# io-board-d-4.net
KiCad netlist of a schematic drawn in EAGLE
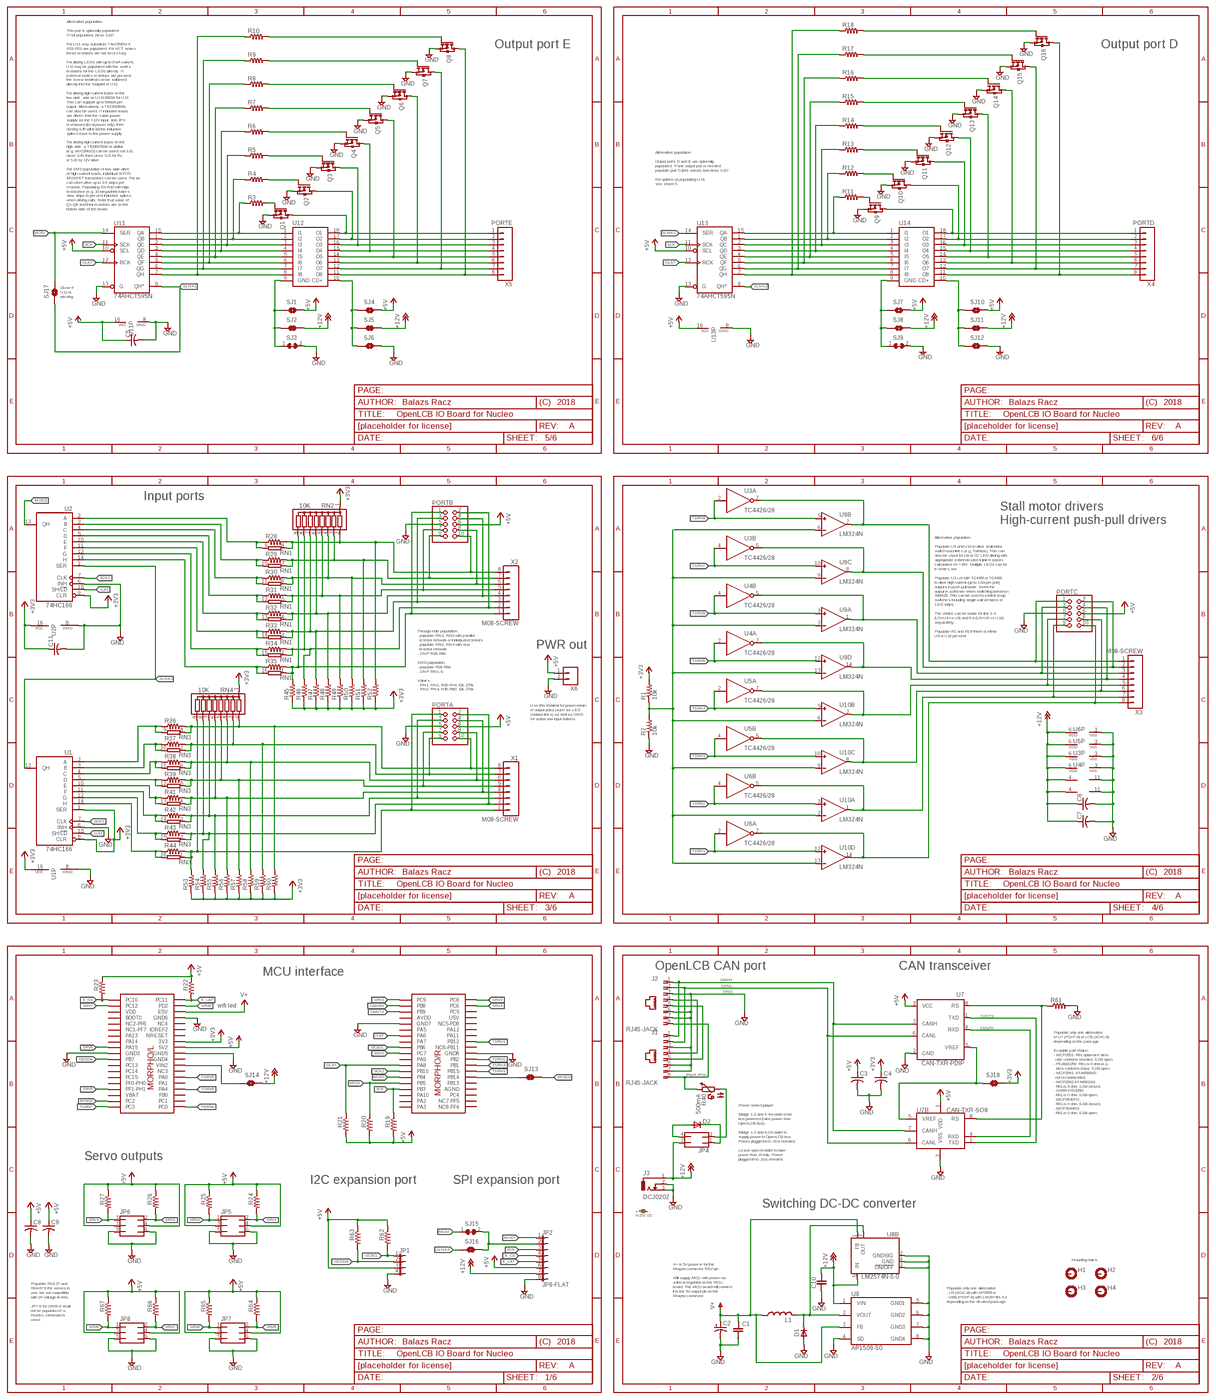
[diagram p0: schematic, sheet 1, overview]
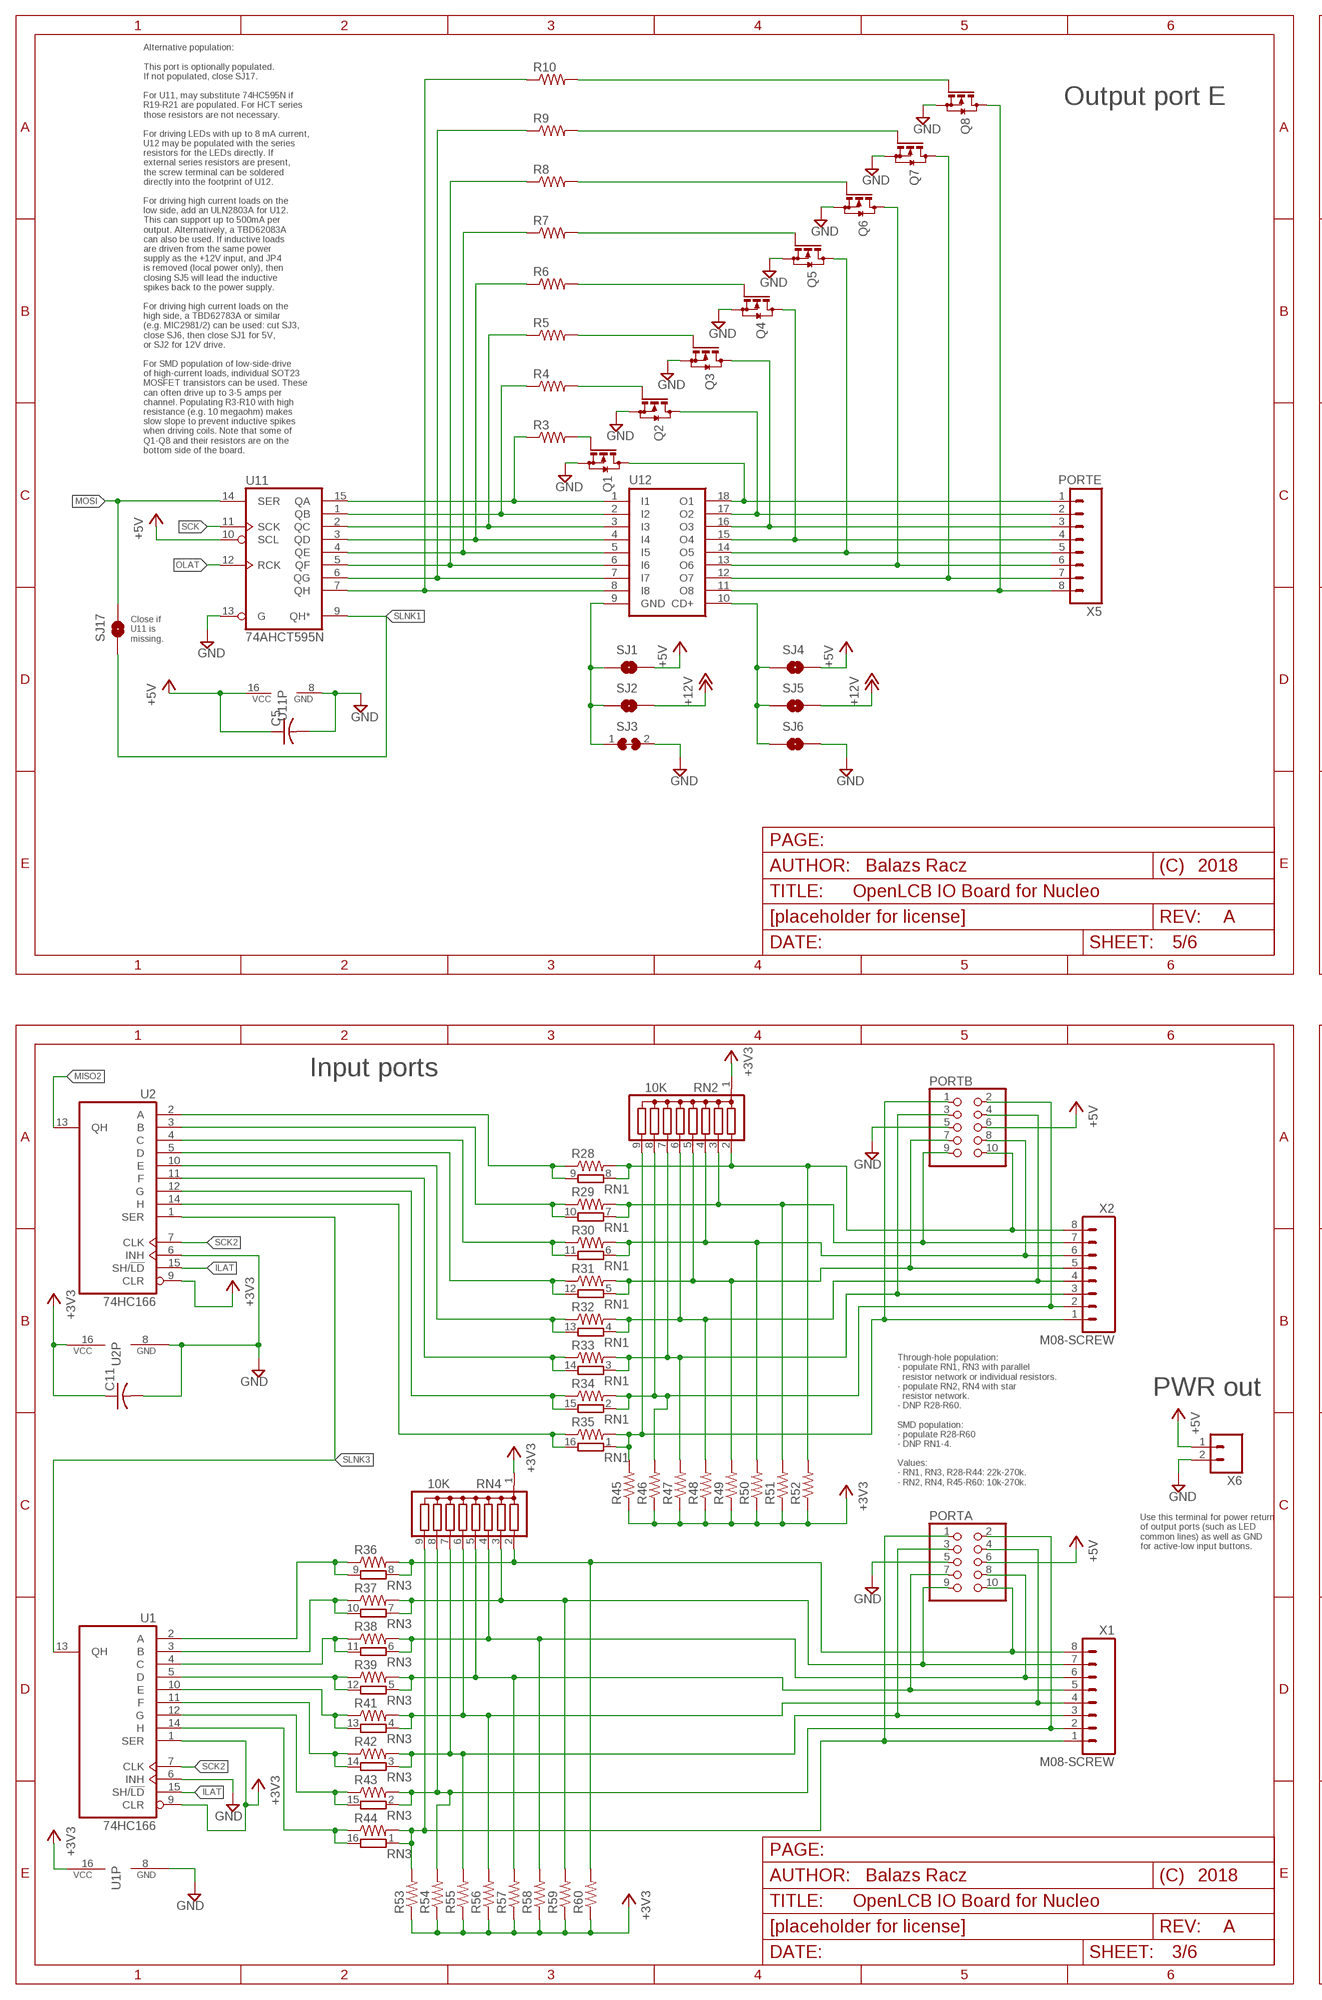
[diagram p1: schematic, sheet 1, part 1 of 4]
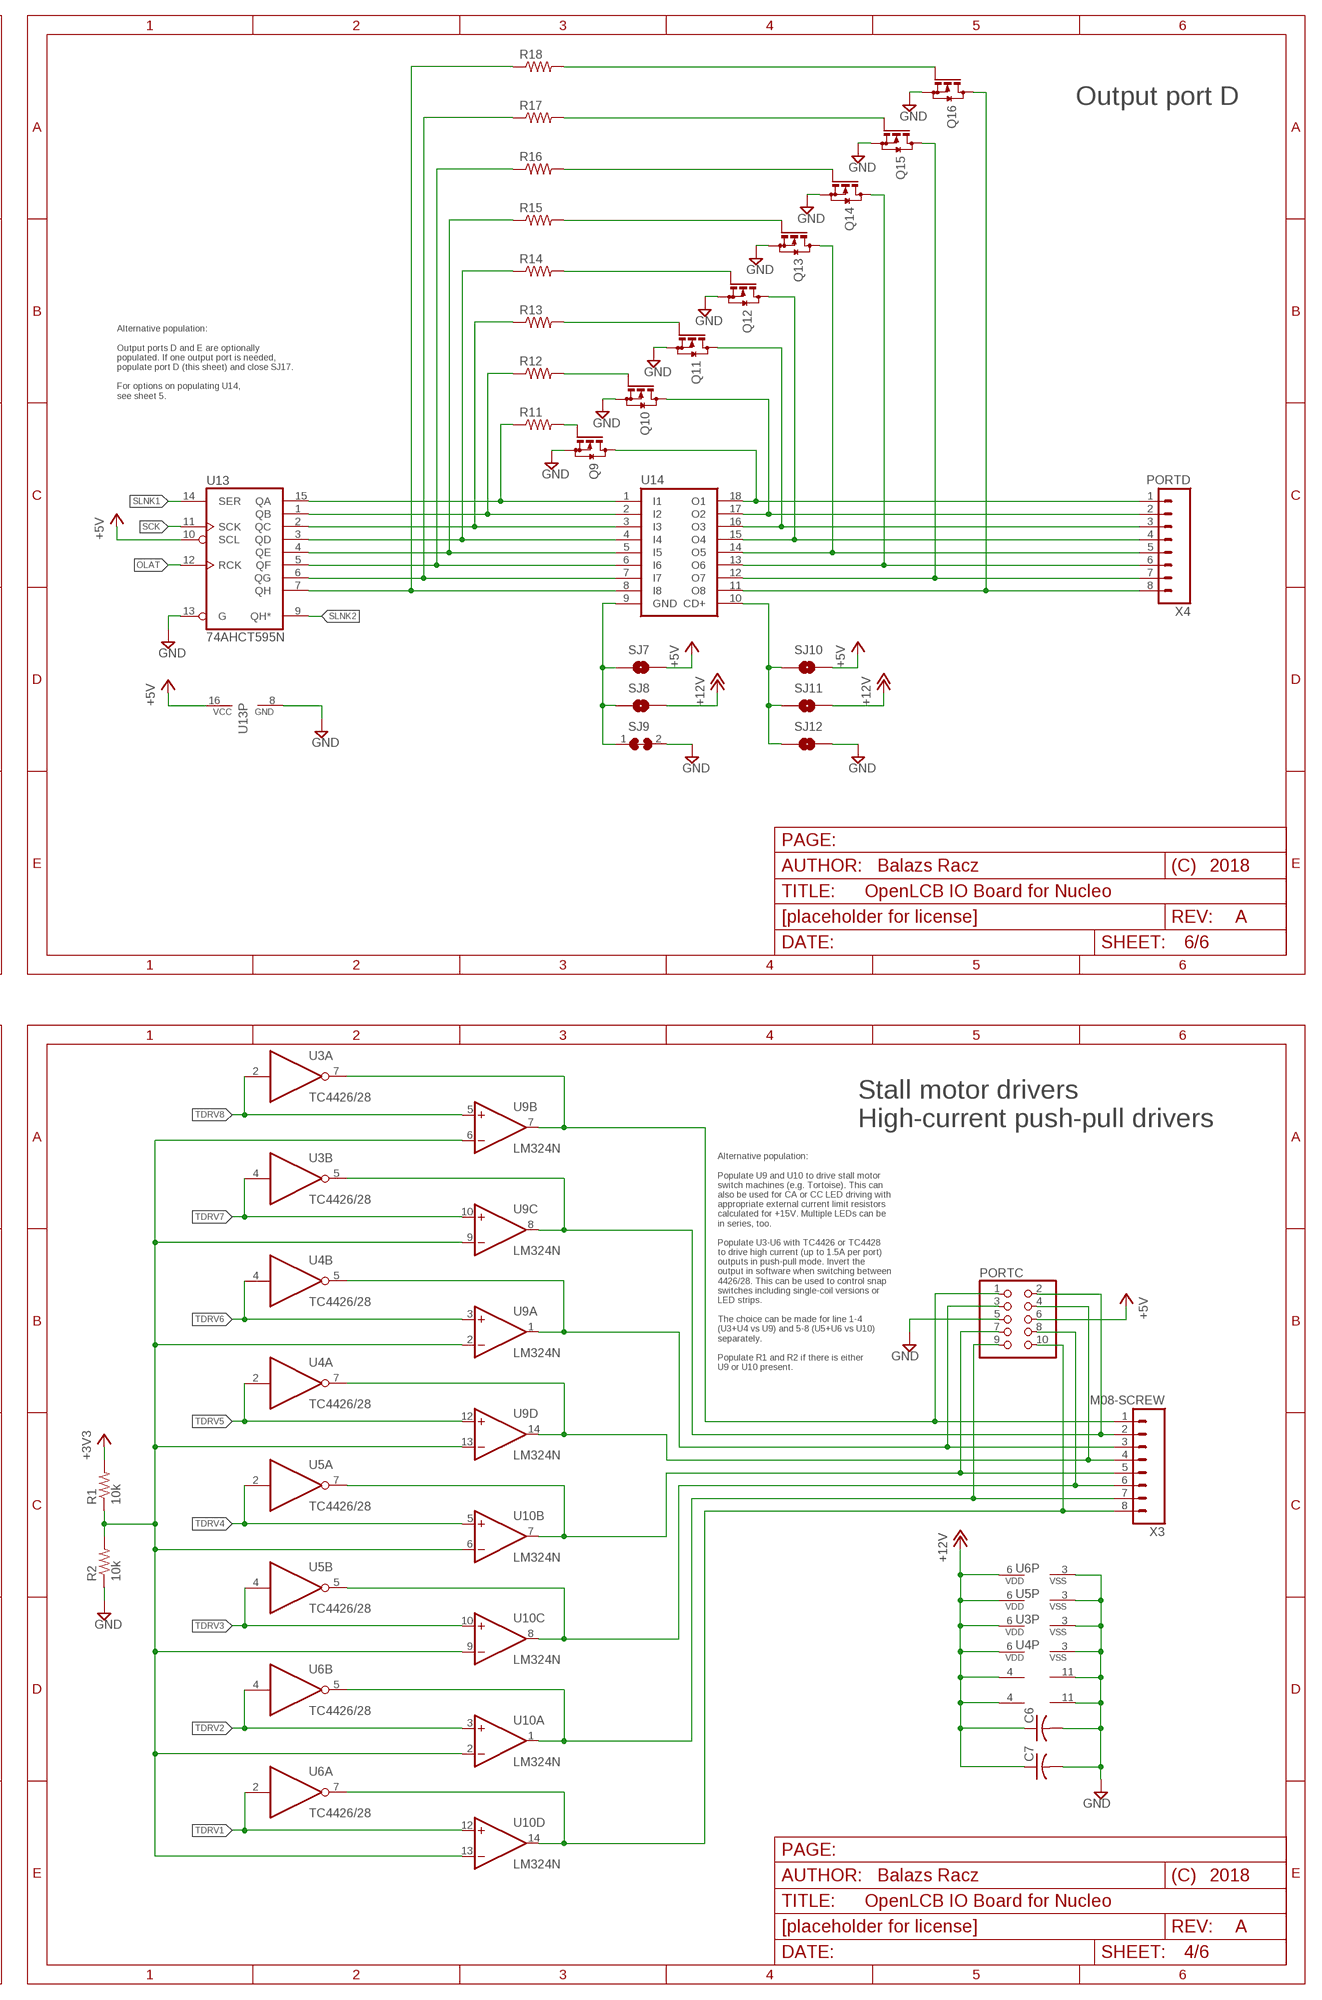
[diagram p2: schematic, sheet 1, part 2 of 4]
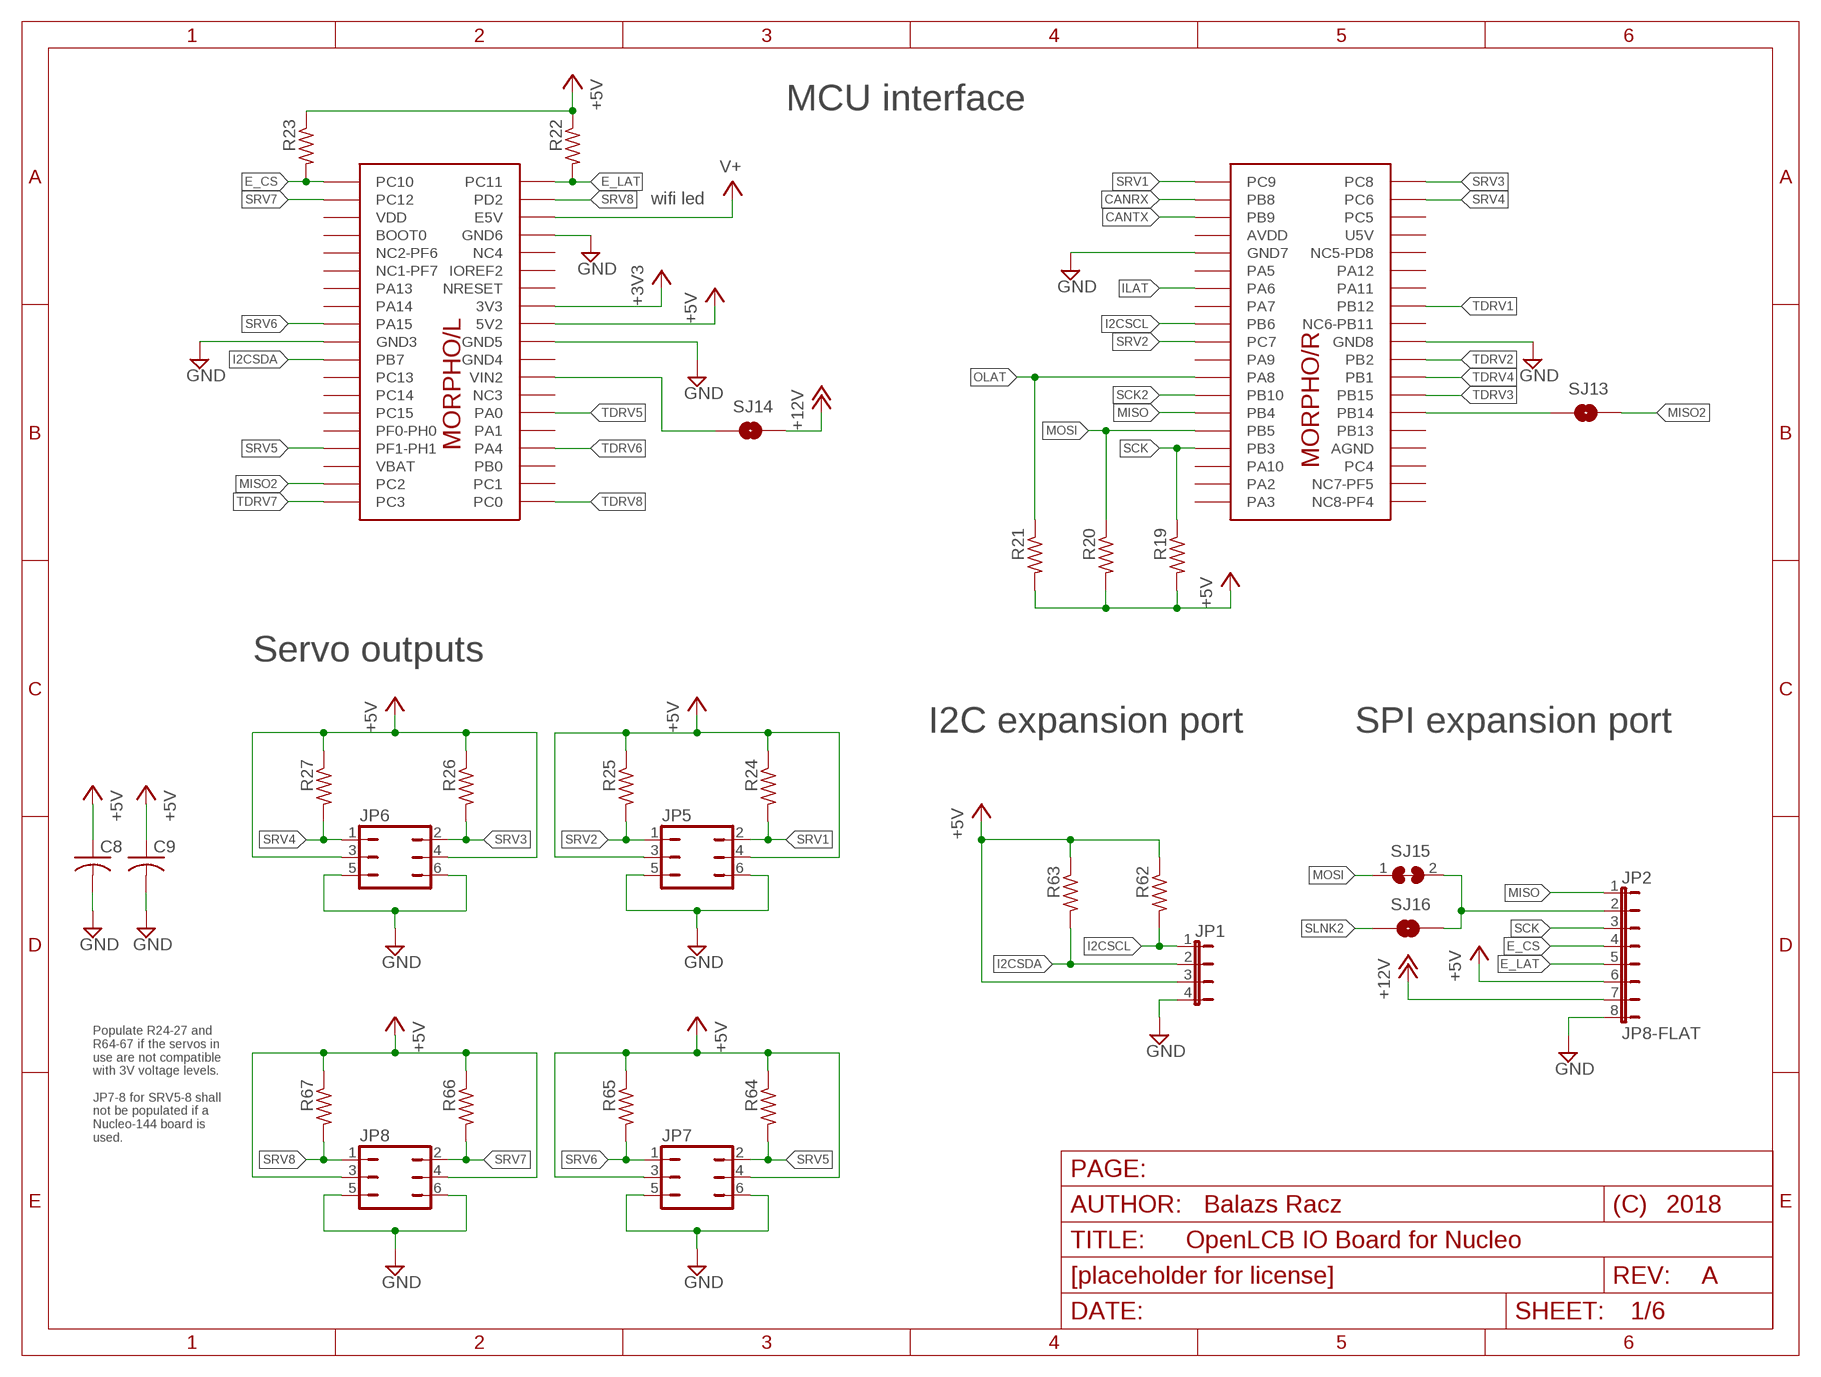
[diagram p3: schematic, sheet 1, part 3 of 4]
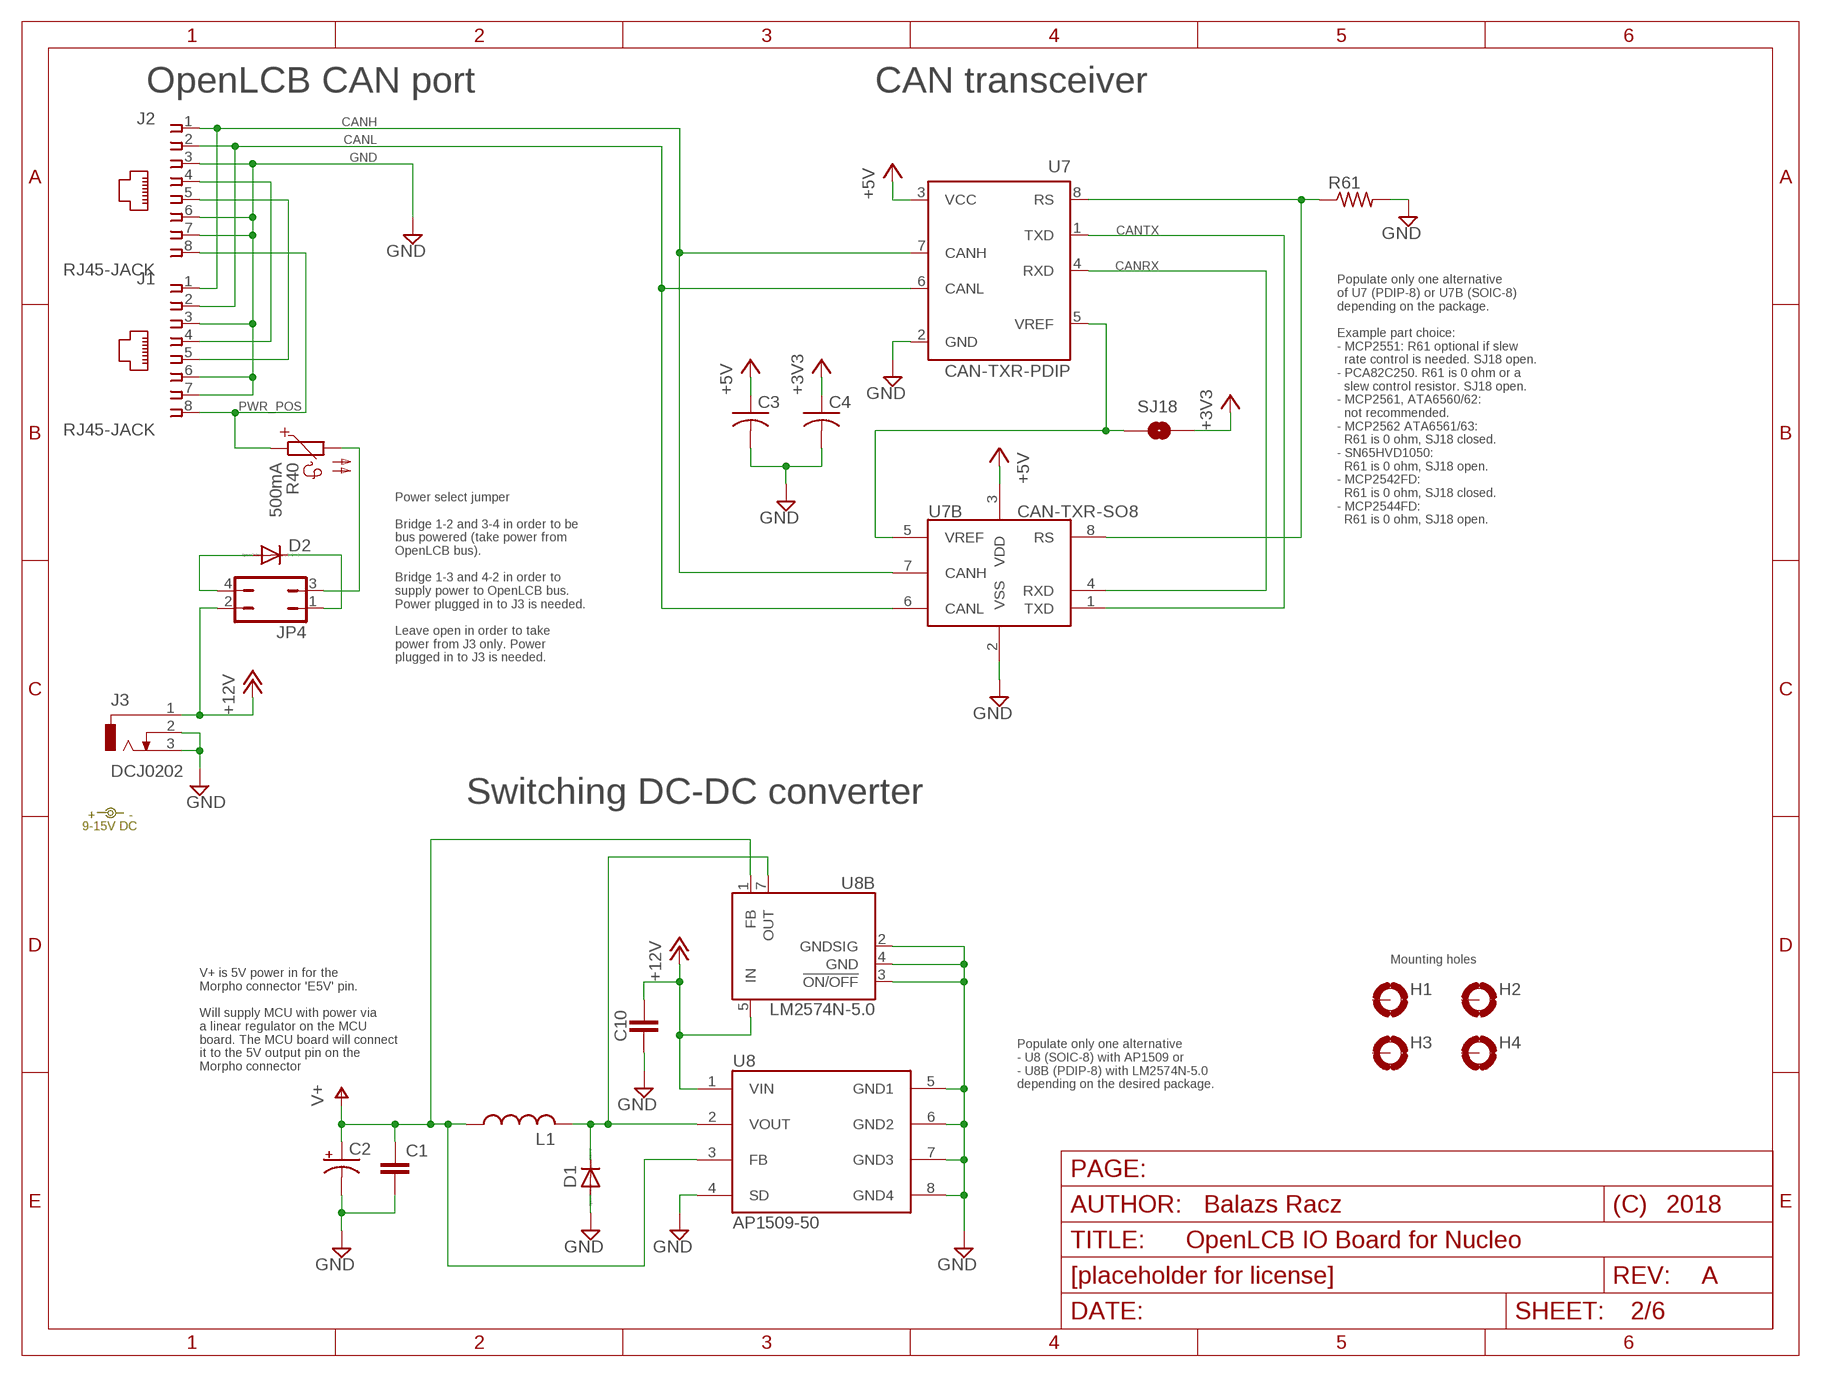
[diagram p4: schematic, sheet 1, part 4 of 4]

(export (version "E")
  (design (tool "Eeschema 10.0.6"))
  (components
    (comp (ref "+12V")
      (value "9-15V DC")
      (footprint "eagle-import:POWER_USAGE")
      (libsource (lib "eagle-import") (part "DOC-POWER_LABEL"))
    )
    (comp (ref "C1")
      (value "C-EUC1206")
      (footprint "eagle-import:C1206")
      (libsource (lib "eagle-import") (part "C-EUC1206"))
    )
    (comp (ref "C2")
      (value "CPOL-USE2.5-5")
      (footprint "eagle-import:E2,5-5")
      (libsource (lib "eagle-import") (part "CPOL-USE2.5-5"))
    )
    (comp (ref "C3")
      (value "C-USC0805")
      (footprint "eagle-import:C0805")
      (libsource (lib "eagle-import") (part "C-USC0805"))
    )
    (comp (ref "C4")
      (value "C-USC0805")
      (footprint "eagle-import:C0805")
      (libsource (lib "eagle-import") (part "C-USC0805"))
    )
    (comp (ref "C5")
      (value "C-USC0805")
      (footprint "eagle-import:C0805")
      (libsource (lib "eagle-import") (part "C-USC0805"))
    )
    (comp (ref "C6")
      (value "C-USC1206")
      (footprint "eagle-import:C1206")
      (libsource (lib "eagle-import") (part "C-USC1206"))
    )
    (comp (ref "C7")
      (value "C-USC1206")
      (footprint "eagle-import:C1206")
      (libsource (lib "eagle-import") (part "C-USC1206"))
    )
    (comp (ref "C8")
      (value "C-USC1206")
      (footprint "eagle-import:C1206")
      (libsource (lib "eagle-import") (part "C-USC1206"))
    )
    (comp (ref "C9")
      (value "C-USC1206")
      (footprint "eagle-import:C1206")
      (libsource (lib "eagle-import") (part "C-USC1206"))
    )
    (comp (ref "C10")
      (value "C-EUC1206")
      (footprint "eagle-import:C1206")
      (libsource (lib "eagle-import") (part "C-EUC1206"))
    )
    (comp (ref "C11")
      (value "C-USC0805")
      (footprint "eagle-import:C0805")
      (libsource (lib "eagle-import") (part "C-USC0805"))
    )
    (comp (ref "D1")
      (value "DIODE-DO41-7.6")
      (footprint "eagle-import:DO41-7.6")
      (libsource (lib "eagle-import") (part "DIODE-DO41-7.6"))
    )
    (comp (ref "D2")
      (value "DIODE-DO41-7.6")
      (footprint "eagle-import:DO41-7.6")
      (libsource (lib "eagle-import") (part "DIODE-DO41-7.6"))
    )
    (comp (ref "H1")
      (value "MOUNT-PAD-ROUND3.3")
      (footprint "eagle-import:3,3-PAD")
      (libsource (lib "eagle-import") (part "MOUNT-PAD-ROUND3.3"))
    )
    (comp (ref "H2")
      (value "MOUNT-PAD-ROUND3.3")
      (footprint "eagle-import:3,3-PAD")
      (libsource (lib "eagle-import") (part "MOUNT-PAD-ROUND3.3"))
    )
    (comp (ref "H3")
      (value "MOUNT-PAD-ROUND3.3")
      (footprint "eagle-import:3,3-PAD")
      (libsource (lib "eagle-import") (part "MOUNT-PAD-ROUND3.3"))
    )
    (comp (ref "H4")
      (value "MOUNT-PAD-ROUND3.3")
      (footprint "eagle-import:3,3-PAD")
      (libsource (lib "eagle-import") (part "MOUNT-PAD-ROUND3.3"))
    )
    (comp (ref "J1")
      (value "RJ45-JACK")
      (footprint "eagle-import:RJ45-PULSE-E5J88")
      (libsource (lib "eagle-import") (part "RJ45-JACKRJ45-PULSE-E5J00"))
    )
    (comp (ref "J2")
      (value "RJ45-JACK")
      (footprint "eagle-import:RJ45-PULSE-E5J88")
      (libsource (lib "eagle-import") (part "RJ45-JACKRJ45-PULSE-E5J00"))
    )
    (comp (ref "J3")
      (value "DCJ0202")
      (footprint "eagle-import:DCJ0202")
      (libsource (lib "eagle-import") (part "DCJ0202"))
    )
    (comp (ref "JP1")
      (value "JP4-FLAT")
      (footprint "eagle-import:JP4F")
      (libsource (lib "eagle-import") (part "JP4-FLAT"))
    )
    (comp (ref "JP2")
      (value "JP8-FLAT")
      (footprint "eagle-import:JP8F")
      (libsource (lib "eagle-import") (part "JP8-FLAT"))
    )
    (comp (ref "JP4")
      (value "JP2Q")
      (footprint "eagle-import:JP2Q")
      (libsource (lib "eagle-import") (part "JP2Q"))
    )
    (comp (ref "JP5")
      (value "JP3Q")
      (footprint "eagle-import:JP3Q")
      (libsource (lib "eagle-import") (part "JP3Q"))
    )
    (comp (ref "JP6")
      (value "JP3Q")
      (footprint "eagle-import:JP3Q")
      (libsource (lib "eagle-import") (part "JP3Q"))
    )
    (comp (ref "JP7")
      (value "JP3Q")
      (footprint "eagle-import:JP3Q")
      (libsource (lib "eagle-import") (part "JP3Q"))
    )
    (comp (ref "JP8")
      (value "JP3Q")
      (footprint "eagle-import:JP3Q")
      (libsource (lib "eagle-import") (part "JP3Q"))
    )
    (comp (ref "L1")
      (value "L-US")
      (footprint "eagle-import:L5-8,5")
      (libsource (lib "eagle-import") (part "L-US"))
    )
    (comp (ref "PORTA")
      (value "PINHD-2X5CN")
      (footprint "eagle-import:CON10M")
      (libsource (lib "eagle-import") (part "PINHD-2X5CN"))
    )
    (comp (ref "PORTB")
      (value "PINHD-2X5CN")
      (footprint "eagle-import:CON10M")
      (libsource (lib "eagle-import") (part "PINHD-2X5CN"))
    )
    (comp (ref "PORTC")
      (value "PINHD-2X5CN")
      (footprint "eagle-import:CON10M")
      (libsource (lib "eagle-import") (part "PINHD-2X5CN"))
    )
    (comp (ref "Q1")
      (value "BSS123")
      (footprint "eagle-import:SOT23")
      (libsource (lib "eagle-import") (part "BSS123"))
    )
    (comp (ref "Q2")
      (value "BSS123")
      (footprint "eagle-import:SOT23")
      (libsource (lib "eagle-import") (part "BSS123"))
    )
    (comp (ref "Q3")
      (value "BSS123")
      (footprint "eagle-import:SOT23")
      (libsource (lib "eagle-import") (part "BSS123"))
    )
    (comp (ref "Q4")
      (value "BSS123")
      (footprint "eagle-import:SOT23")
      (libsource (lib "eagle-import") (part "BSS123"))
    )
    (comp (ref "Q5")
      (value "BSS123")
      (footprint "eagle-import:SOT23")
      (libsource (lib "eagle-import") (part "BSS123"))
    )
    (comp (ref "Q6")
      (value "BSS123")
      (footprint "eagle-import:SOT23")
      (libsource (lib "eagle-import") (part "BSS123"))
    )
    (comp (ref "Q7")
      (value "BSS123")
      (footprint "eagle-import:SOT23")
      (libsource (lib "eagle-import") (part "BSS123"))
    )
    (comp (ref "Q8")
      (value "BSS123")
      (footprint "eagle-import:SOT23")
      (libsource (lib "eagle-import") (part "BSS123"))
    )
    (comp (ref "Q9")
      (value "BSS123")
      (footprint "eagle-import:SOT23")
      (libsource (lib "eagle-import") (part "BSS123"))
    )
    (comp (ref "Q10")
      (value "BSS123")
      (footprint "eagle-import:SOT23")
      (libsource (lib "eagle-import") (part "BSS123"))
    )
    (comp (ref "Q11")
      (value "BSS123")
      (footprint "eagle-import:SOT23")
      (libsource (lib "eagle-import") (part "BSS123"))
    )
    (comp (ref "Q12")
      (value "BSS123")
      (footprint "eagle-import:SOT23")
      (libsource (lib "eagle-import") (part "BSS123"))
    )
    (comp (ref "Q13")
      (value "BSS123")
      (footprint "eagle-import:SOT23")
      (libsource (lib "eagle-import") (part "BSS123"))
    )
    (comp (ref "Q14")
      (value "BSS123")
      (footprint "eagle-import:SOT23")
      (libsource (lib "eagle-import") (part "BSS123"))
    )
    (comp (ref "Q15")
      (value "BSS123")
      (footprint "eagle-import:SOT23")
      (libsource (lib "eagle-import") (part "BSS123"))
    )
    (comp (ref "Q16")
      (value "BSS123")
      (footprint "eagle-import:SOT23")
      (libsource (lib "eagle-import") (part "BSS123"))
    )
    (comp (ref "R1")
      (value "10k")
      (footprint "eagle-import:R0805")
      (libsource (lib "eagle-import") (part "R-US_R0805"))
    )
    (comp (ref "R2")
      (value "10k")
      (footprint "eagle-import:R0805")
      (libsource (lib "eagle-import") (part "R-US_R0805"))
    )
    (comp (ref "R3")
      (value "R-US_R0603")
      (footprint "eagle-import:R0603")
      (libsource (lib "eagle-import") (part "R-US_R0603"))
    )
    (comp (ref "R4")
      (value "R-US_R0603")
      (footprint "eagle-import:R0603")
      (libsource (lib "eagle-import") (part "R-US_R0603"))
    )
    (comp (ref "R5")
      (value "R-US_R0603")
      (footprint "eagle-import:R0603")
      (libsource (lib "eagle-import") (part "R-US_R0603"))
    )
    (comp (ref "R6")
      (value "R-US_R0603")
      (footprint "eagle-import:R0603")
      (libsource (lib "eagle-import") (part "R-US_R0603"))
    )
    (comp (ref "R7")
      (value "R-US_R0603")
      (footprint "eagle-import:R0603")
      (libsource (lib "eagle-import") (part "R-US_R0603"))
    )
    (comp (ref "R8")
      (value "R-US_R0603")
      (footprint "eagle-import:R0603")
      (libsource (lib "eagle-import") (part "R-US_R0603"))
    )
    (comp (ref "R9")
      (value "R-US_R0603")
      (footprint "eagle-import:R0603")
      (libsource (lib "eagle-import") (part "R-US_R0603"))
    )
    (comp (ref "R10")
      (value "R-US_R0603")
      (footprint "eagle-import:R0603")
      (libsource (lib "eagle-import") (part "R-US_R0603"))
    )
    (comp (ref "R11")
      (value "R-US_R0603")
      (footprint "eagle-import:R0603")
      (libsource (lib "eagle-import") (part "R-US_R0603"))
    )
    (comp (ref "R12")
      (value "R-US_R0603")
      (footprint "eagle-import:R0603")
      (libsource (lib "eagle-import") (part "R-US_R0603"))
    )
    (comp (ref "R13")
      (value "R-US_R0603")
      (footprint "eagle-import:R0603")
      (libsource (lib "eagle-import") (part "R-US_R0603"))
    )
    (comp (ref "R14")
      (value "R-US_R0603")
      (footprint "eagle-import:R0603")
      (libsource (lib "eagle-import") (part "R-US_R0603"))
    )
    (comp (ref "R15")
      (value "R-US_R0603")
      (footprint "eagle-import:R0603")
      (libsource (lib "eagle-import") (part "R-US_R0603"))
    )
    (comp (ref "R16")
      (value "R-US_R0603")
      (footprint "eagle-import:R0603")
      (libsource (lib "eagle-import") (part "R-US_R0603"))
    )
    (comp (ref "R17")
      (value "R-US_R0603")
      (footprint "eagle-import:R0603")
      (libsource (lib "eagle-import") (part "R-US_R0603"))
    )
    (comp (ref "R18")
      (value "R-US_R0603")
      (footprint "eagle-import:R0603")
      (libsource (lib "eagle-import") (part "R-US_R0603"))
    )
    (comp (ref "R19")
      (value "R-US_R0805")
      (footprint "eagle-import:R0805")
      (libsource (lib "eagle-import") (part "rcl_334_R-US_R0805"))
    )
    (comp (ref "R20")
      (value "R-US_R0805")
      (footprint "eagle-import:R0805")
      (libsource (lib "eagle-import") (part "rcl_334_R-US_R0805"))
    )
    (comp (ref "R21")
      (value "R-US_R0805")
      (footprint "eagle-import:R0805")
      (libsource (lib "eagle-import") (part "rcl_334_R-US_R0805"))
    )
    (comp (ref "R22")
      (value "R-US_R0805")
      (footprint "eagle-import:R0805")
      (libsource (lib "eagle-import") (part "rcl_334_R-US_R0805"))
    )
    (comp (ref "R23")
      (value "R-US_R0805")
      (footprint "eagle-import:R0805")
      (libsource (lib "eagle-import") (part "rcl_334_R-US_R0805"))
    )
    (comp (ref "R24")
      (value "R-US_R0805")
      (footprint "eagle-import:R0805")
      (libsource (lib "eagle-import") (part "rcl_334_R-US_R0805"))
    )
    (comp (ref "R25")
      (value "R-US_R0805")
      (footprint "eagle-import:R0805")
      (libsource (lib "eagle-import") (part "rcl_334_R-US_R0805"))
    )
    (comp (ref "R26")
      (value "R-US_R0805")
      (footprint "eagle-import:R0805")
      (libsource (lib "eagle-import") (part "rcl_334_R-US_R0805"))
    )
    (comp (ref "R27")
      (value "R-US_R0805")
      (footprint "eagle-import:R0805")
      (libsource (lib "eagle-import") (part "rcl_334_R-US_R0805"))
    )
    (comp (ref "R28")
      (value "R-US_R0603")
      (footprint "eagle-import:R0603")
      (libsource (lib "eagle-import") (part "rcl_334_R-US_R0603"))
    )
    (comp (ref "R29")
      (value "R-US_R0603")
      (footprint "eagle-import:R0603")
      (libsource (lib "eagle-import") (part "rcl_334_R-US_R0603"))
    )
    (comp (ref "R30")
      (value "R-US_R0603")
      (footprint "eagle-import:R0603")
      (libsource (lib "eagle-import") (part "rcl_334_R-US_R0603"))
    )
    (comp (ref "R31")
      (value "R-US_R0603")
      (footprint "eagle-import:R0603")
      (libsource (lib "eagle-import") (part "rcl_334_R-US_R0603"))
    )
    (comp (ref "R32")
      (value "R-US_R0603")
      (footprint "eagle-import:R0603")
      (libsource (lib "eagle-import") (part "rcl_334_R-US_R0603"))
    )
    (comp (ref "R33")
      (value "R-US_R0603")
      (footprint "eagle-import:R0603")
      (libsource (lib "eagle-import") (part "rcl_334_R-US_R0603"))
    )
    (comp (ref "R34")
      (value "R-US_R0603")
      (footprint "eagle-import:R0603")
      (libsource (lib "eagle-import") (part "rcl_334_R-US_R0603"))
    )
    (comp (ref "R35")
      (value "R-US_R0603")
      (footprint "eagle-import:R0603")
      (libsource (lib "eagle-import") (part "rcl_334_R-US_R0603"))
    )
    (comp (ref "R36")
      (value "R-US_R0603")
      (footprint "eagle-import:R0603")
      (libsource (lib "eagle-import") (part "rcl_334_R-US_R0603"))
    )
    (comp (ref "R37")
      (value "R-US_R0603")
      (footprint "eagle-import:R0603")
      (libsource (lib "eagle-import") (part "rcl_334_R-US_R0603"))
    )
    (comp (ref "R38")
      (value "R-US_R0603")
      (footprint "eagle-import:R0603")
      (libsource (lib "eagle-import") (part "rcl_334_R-US_R0603"))
    )
    (comp (ref "R39")
      (value "R-US_R0603")
      (footprint "eagle-import:R0603")
      (libsource (lib "eagle-import") (part "rcl_334_R-US_R0603"))
    )
    (comp (ref "R40")
      (value "500mA")
      (footprint "eagle-import:PTC1812")
      (libsource (lib "eagle-import") (part "PTC_1812"))
    )
    (comp (ref "R41")
      (value "R-US_R0603")
      (footprint "eagle-import:R0603")
      (libsource (lib "eagle-import") (part "rcl_334_R-US_R0603"))
    )
    (comp (ref "R42")
      (value "R-US_R0603")
      (footprint "eagle-import:R0603")
      (libsource (lib "eagle-import") (part "rcl_334_R-US_R0603"))
    )
    (comp (ref "R43")
      (value "R-US_R0603")
      (footprint "eagle-import:R0603")
      (libsource (lib "eagle-import") (part "rcl_334_R-US_R0603"))
    )
    (comp (ref "R44")
      (value "R-US_R0603")
      (footprint "eagle-import:R0603")
      (libsource (lib "eagle-import") (part "rcl_334_R-US_R0603"))
    )
    (comp (ref "R45")
      (value "R-US")
      (footprint "eagle-import:R0603")
      (libsource (lib "eagle-import") (part "R-US"))
    )
    (comp (ref "R46")
      (value "R-US")
      (footprint "eagle-import:R0603")
      (libsource (lib "eagle-import") (part "R-US"))
    )
    (comp (ref "R47")
      (value "R-US")
      (footprint "eagle-import:R0603")
      (libsource (lib "eagle-import") (part "R-US"))
    )
    (comp (ref "R48")
      (value "R-US")
      (footprint "eagle-import:R0603")
      (libsource (lib "eagle-import") (part "R-US"))
    )
    (comp (ref "R49")
      (value "R-US")
      (footprint "eagle-import:R0603")
      (libsource (lib "eagle-import") (part "R-US"))
    )
    (comp (ref "R50")
      (value "R-US")
      (footprint "eagle-import:R0603")
      (libsource (lib "eagle-import") (part "R-US"))
    )
    (comp (ref "R51")
      (value "R-US")
      (footprint "eagle-import:R0603")
      (libsource (lib "eagle-import") (part "R-US"))
    )
    (comp (ref "R52")
      (value "R-US")
      (footprint "eagle-import:R0603")
      (libsource (lib "eagle-import") (part "R-US"))
    )
    (comp (ref "R53")
      (value "R-US")
      (footprint "eagle-import:R0603")
      (libsource (lib "eagle-import") (part "R-US"))
    )
    (comp (ref "R54")
      (value "R-US")
      (footprint "eagle-import:R0603")
      (libsource (lib "eagle-import") (part "R-US"))
    )
    (comp (ref "R55")
      (value "R-US")
      (footprint "eagle-import:R0603")
      (libsource (lib "eagle-import") (part "R-US"))
    )
    (comp (ref "R56")
      (value "R-US")
      (footprint "eagle-import:R0603")
      (libsource (lib "eagle-import") (part "R-US"))
    )
    (comp (ref "R57")
      (value "R-US")
      (footprint "eagle-import:R0603")
      (libsource (lib "eagle-import") (part "R-US"))
    )
    (comp (ref "R58")
      (value "R-US")
      (footprint "eagle-import:R0603")
      (libsource (lib "eagle-import") (part "R-US"))
    )
    (comp (ref "R59")
      (value "R-US")
      (footprint "eagle-import:R0603")
      (libsource (lib "eagle-import") (part "R-US"))
    )
    (comp (ref "R60")
      (value "R-US")
      (footprint "eagle-import:R0603")
      (libsource (lib "eagle-import") (part "R-US"))
    )
    (comp (ref "R61")
      (value "R-US_R0805")
      (footprint "eagle-import:R0805")
      (libsource (lib "eagle-import") (part "rcl_334_R-US_R0805"))
    )
    (comp (ref "R62")
      (value "R-US_R0805")
      (footprint "eagle-import:R0805")
      (libsource (lib "eagle-import") (part "rcl_334_R-US_R0805"))
    )
    (comp (ref "R63")
      (value "R-US_R0805")
      (footprint "eagle-import:R0805")
      (libsource (lib "eagle-import") (part "rcl_334_R-US_R0805"))
    )
    (comp (ref "R64")
      (value "R-US_R0805")
      (footprint "eagle-import:R0805")
      (libsource (lib "eagle-import") (part "rcl_334_R-US_R0805"))
    )
    (comp (ref "R65")
      (value "R-US_R0805")
      (footprint "eagle-import:R0805")
      (libsource (lib "eagle-import") (part "rcl_334_R-US_R0805"))
    )
    (comp (ref "R66")
      (value "R-US_R0805")
      (footprint "eagle-import:R0805")
      (libsource (lib "eagle-import") (part "rcl_334_R-US_R0805"))
    )
    (comp (ref "R67")
      (value "R-US_R0805")
      (footprint "eagle-import:R0805")
      (libsource (lib "eagle-import") (part "rcl_334_R-US_R0805"))
    )
    (comp (ref "RN1")
      (value "8R-P")
      (footprint "eagle-import:DIL16")
      (libsource (lib "eagle-import") (part "8R-P"))
    )
    (comp (ref "RN2")
      (value "10K")
      (footprint "eagle-import:SIL9")
      (libsource (lib "eagle-import") (part "G08R"))
    )
    (comp (ref "RN3")
      (value "8R-P")
      (footprint "eagle-import:DIL16")
      (libsource (lib "eagle-import") (part "8R-P"))
    )
    (comp (ref "RN4")
      (value "10K")
      (footprint "eagle-import:SIL9")
      (libsource (lib "eagle-import") (part "G08R"))
    )
    (comp (ref "SJ1")
      (value "SJRND2")
      (footprint "eagle-import:SJ_RND2")
      (libsource (lib "eagle-import") (part "SJRND2"))
    )
    (comp (ref "SJ2")
      (value "SJRND2")
      (footprint "eagle-import:SJ_RND2")
      (libsource (lib "eagle-import") (part "SJRND2"))
    )
    (comp (ref "SJ3")
      (value "SJ-C")
      (footprint "eagle-import:SJW-C")
      (libsource (lib "eagle-import") (part "SJ-C"))
    )
    (comp (ref "SJ4")
      (value "SJRND2")
      (footprint "eagle-import:SJ_RND2")
      (libsource (lib "eagle-import") (part "SJRND2"))
    )
    (comp (ref "SJ5")
      (value "SJRND2")
      (footprint "eagle-import:SJ_RND2")
      (libsource (lib "eagle-import") (part "SJRND2"))
    )
    (comp (ref "SJ6")
      (value "SJRND2")
      (footprint "eagle-import:SJ_RND2")
      (libsource (lib "eagle-import") (part "SJRND2"))
    )
    (comp (ref "SJ7")
      (value "SJRND2")
      (footprint "eagle-import:SJ_RND2")
      (libsource (lib "eagle-import") (part "SJRND2"))
    )
    (comp (ref "SJ8")
      (value "SJRND2")
      (footprint "eagle-import:SJ_RND2")
      (libsource (lib "eagle-import") (part "SJRND2"))
    )
    (comp (ref "SJ9")
      (value "SJ-C")
      (footprint "eagle-import:SJW-C")
      (libsource (lib "eagle-import") (part "SJ-C"))
    )
    (comp (ref "SJ10")
      (value "SJRND2")
      (footprint "eagle-import:SJ_RND2")
      (libsource (lib "eagle-import") (part "SJRND2"))
    )
    (comp (ref "SJ11")
      (value "SJRND2")
      (footprint "eagle-import:SJ_RND2")
      (libsource (lib "eagle-import") (part "SJRND2"))
    )
    (comp (ref "SJ12")
      (value "SJRND2")
      (footprint "eagle-import:SJ_RND2")
      (libsource (lib "eagle-import") (part "SJRND2"))
    )
    (comp (ref "SJ13")
      (value "SJRND2")
      (footprint "eagle-import:SJ_RND2")
      (libsource (lib "eagle-import") (part "SJRND2"))
    )
    (comp (ref "SJ14")
      (value "SJRND2")
      (footprint "eagle-import:SJ_RND2")
      (libsource (lib "eagle-import") (part "SJRND2"))
    )
    (comp (ref "SJ15")
      (value "SJ-C")
      (footprint "eagle-import:SJW-C")
      (libsource (lib "eagle-import") (part "SJ-C"))
    )
    (comp (ref "SJ16")
      (value "SJRND2")
      (footprint "eagle-import:SJ_RND2")
      (libsource (lib "eagle-import") (part "SJRND2"))
    )
    (comp (ref "SJ17")
      (value "SJRND2")
      (footprint "eagle-import:SJ_RND2")
      (libsource (lib "eagle-import") (part "SJRND2"))
    )
    (comp (ref "SJ18")
      (value "SJRND2")
      (footprint "eagle-import:SJ_RND2")
      (libsource (lib "eagle-import") (part "SJRND2"))
    )
    (comp (ref "U$1")
      (value "NUCLEO_64_GENERIC")
      (footprint "eagle-import:NUCLEO_BRD_BASE64")
      (libsource (lib "eagle-import") (part "NUCLEO_64_GENERIC"))
    )
    (comp (ref "U1")
      (value "74HC166")
      (footprint "eagle-import:DIL16")
      (libsource (lib "eagle-import") (part "74166N"))
    )
    (comp (ref "U2")
      (value "74HC166")
      (footprint "eagle-import:DIL16")
      (libsource (lib "eagle-import") (part "74166N"))
    )
    (comp (ref "U3")
      (value "TC4426/28")
      (footprint "eagle-import:DIL08-LONG")
      (libsource (lib "eagle-import") (part "TC4426APDIP"))
    )
    (comp (ref "U4")
      (value "TC4426/28")
      (footprint "eagle-import:DIL08-LONG")
      (libsource (lib "eagle-import") (part "TC4426APDIP"))
    )
    (comp (ref "U5")
      (value "TC4426/28")
      (footprint "eagle-import:DIL08-LONG")
      (libsource (lib "eagle-import") (part "TC4426APDIP"))
    )
    (comp (ref "U6")
      (value "TC4426/28")
      (footprint "eagle-import:DIL08-LONG")
      (libsource (lib "eagle-import") (part "TC4426APDIP"))
    )
    (comp (ref "U7")
      (value "CAN-TXR-PDIP")
      (footprint "eagle-import:DIL08")
      (libsource (lib "eagle-import") (part "PCA82C250"))
    )
    (comp (ref "U7B")
      (value "CAN-TXR-SO8")
      (footprint "eagle-import:SO-08")
      (libsource (lib "eagle-import") (part "MCP2551-SN"))
    )
    (comp (ref "U8")
      (value "AP1509-50")
      (footprint "eagle-import:SO-08")
      (libsource (lib "eagle-import") (part "AP1509"))
    )
    (comp (ref "U8B")
      (value "LM2574N-5.0")
      (footprint "eagle-import:DIL08")
      (libsource (lib "eagle-import") (part "LM2574?-N5.0"))
    )
    (comp (ref "U9")
      (value "LM324N")
      (footprint "eagle-import:DIL14")
      (libsource (lib "eagle-import") (part "LM324N"))
    )
    (comp (ref "U10")
      (value "LM324N")
      (footprint "eagle-import:DIL14")
      (libsource (lib "eagle-import") (part "LM324N"))
    )
    (comp (ref "U11")
      (value "74AHCT595N")
      (footprint "eagle-import:DIL16")
      (libsource (lib "eagle-import") (part "74595NHCT"))
    )
    (comp (ref "U12")
      (value "ULN2803A")
      (footprint "eagle-import:DIL18-THIN")
      (libsource (lib "eagle-import") (part "ULN2803A"))
    )
    (comp (ref "U13")
      (value "74AHCT595N")
      (footprint "eagle-import:DIL16")
      (libsource (lib "eagle-import") (part "74595NHCT"))
    )
    (comp (ref "U14")
      (value "ULN2803A")
      (footprint "eagle-import:DIL18-THIN")
      (libsource (lib "eagle-import") (part "ULN2803A"))
    )
    (comp (ref "X1")
      (value "M08-SCREW")
      (footprint "eagle-import:1X08_TERMINAL")
      (libsource (lib "eagle-import") (part "M08-SCREW"))
    )
    (comp (ref "X2")
      (value "M08-SCREW")
      (footprint "eagle-import:1X08_TERMINAL")
      (libsource (lib "eagle-import") (part "M08-SCREW"))
    )
    (comp (ref "X3")
      (value "M08-SCREW")
      (footprint "eagle-import:1X08_TERMINAL")
      (libsource (lib "eagle-import") (part "M08-SCREW"))
    )
    (comp (ref "X4")
      (value "PORTD")
      (footprint "eagle-import:1X08_TERMINAL")
      (libsource (lib "eagle-import") (part "M08-SCREW"))
    )
    (comp (ref "X5")
      (value "PORTE")
      (footprint "eagle-import:1X08_TERMINAL")
      (libsource (lib "eagle-import") (part "M08-SCREW"))
    )
    (comp (ref "X6")
      (value "CONNECTOR-M023.5MM-LOCK")
      (footprint "eagle-import:SCREWTERMINAL-3.5MM-2_LOCK")
      (libsource (lib "eagle-import") (part "CONNECTOR-M023.5MM-LOCK"))
    )
  )
  (nets
    (net (code "1") (name "+3V3") (class "Default")
      (node (ref "C11") (pin "1") (pinfunction "1_1") (pintype "passive"))
      (node (ref "C4") (pin "1") (pinfunction "1_1") (pintype "passive"))
      (node (ref "R1") (pin "2") (pinfunction "2_2") (pintype "passive"))
      (node (ref "R45") (pin "1") (pinfunction "1_1") (pintype "passive"))
      (node (ref "R46") (pin "1") (pinfunction "1_1") (pintype "passive"))
      (node (ref "R47") (pin "1") (pinfunction "1_1") (pintype "passive"))
      (node (ref "R48") (pin "1") (pinfunction "1_1") (pintype "passive"))
      (node (ref "R49") (pin "1") (pinfunction "1_1") (pintype "passive"))
      (node (ref "R50") (pin "1") (pinfunction "1_1") (pintype "passive"))
      (node (ref "R51") (pin "1") (pinfunction "1_1") (pintype "passive"))
      (node (ref "R52") (pin "1") (pinfunction "1_1") (pintype "passive"))
      (node (ref "R53") (pin "1") (pinfunction "1_1") (pintype "passive"))
      (node (ref "R54") (pin "1") (pinfunction "1_1") (pintype "passive"))
      (node (ref "R55") (pin "1") (pinfunction "1_1") (pintype "passive"))
      (node (ref "R56") (pin "1") (pinfunction "1_1") (pintype "passive"))
      (node (ref "R57") (pin "1") (pinfunction "1_1") (pintype "passive"))
      (node (ref "R58") (pin "1") (pinfunction "1_1") (pintype "passive"))
      (node (ref "R59") (pin "1") (pinfunction "1_1") (pintype "passive"))
      (node (ref "R60") (pin "1") (pinfunction "1_1") (pintype "passive"))
      (node (ref "RN2") (pin "1") (pinfunction "1_1") (pintype "passive"))
      (node (ref "RN4") (pin "1") (pinfunction "1_1") (pintype "passive"))
      (node (ref "SJ18") (pin "P$1") (pinfunction "1_P$1") (pintype "passive"))
      (node (ref "U$1") (pin "3V3") (pinfunction "3V3_3V3") (pintype "power_in"))
      (node (ref "U1") (pin "1") (pinfunction "SER_1") (pintype "input"))
      (node (ref "U1") (pin "16") (pinfunction "VCC_16") (pintype "power_in"))
      (node (ref "U1") (pin "9") (pinfunction "CLR_9") (pintype "input"))
      (node (ref "U2") (pin "16") (pinfunction "VCC_16") (pintype "power_in"))
      (node (ref "U2") (pin "9") (pinfunction "CLR_9") (pintype "input"))
    )
    (net (code "2") (name "+5V") (class "Default")
      (node (ref "C3") (pin "1") (pinfunction "1_1") (pintype "passive"))
      (node (ref "C5") (pin "1") (pinfunction "1_1") (pintype "passive"))
      (node (ref "C8") (pin "1") (pinfunction "1_1") (pintype "passive"))
      (node (ref "C9") (pin "1") (pinfunction "1_1") (pintype "passive"))
      (node (ref "JP1") (pin "3") (pinfunction "3_3") (pintype "passive"))
      (node (ref "JP2") (pin "6") (pinfunction "6_6") (pintype "passive"))
      (node (ref "JP5") (pin "3") (pinfunction "3_3") (pintype "passive"))
      (node (ref "JP5") (pin "4") (pinfunction "4_4") (pintype "passive"))
      (node (ref "JP6") (pin "3") (pinfunction "3_3") (pintype "passive"))
      (node (ref "JP6") (pin "4") (pinfunction "4_4") (pintype "passive"))
      (node (ref "JP7") (pin "3") (pinfunction "3_3") (pintype "passive"))
      (node (ref "JP7") (pin "4") (pinfunction "4_4") (pintype "passive"))
      (node (ref "JP8") (pin "3") (pinfunction "3_3") (pintype "passive"))
      (node (ref "JP8") (pin "4") (pinfunction "4_4") (pintype "passive"))
      (node (ref "PORTA") (pin "6") (pinfunction "6_6") (pintype "passive"))
      (node (ref "PORTB") (pin "6") (pinfunction "6_6") (pintype "passive"))
      (node (ref "PORTC") (pin "6") (pinfunction "6_6") (pintype "passive"))
      (node (ref "R19") (pin "2") (pinfunction "2_2") (pintype "passive"))
      (node (ref "R20") (pin "2") (pinfunction "2_2") (pintype "passive"))
      (node (ref "R21") (pin "2") (pinfunction "2_2") (pintype "passive"))
      (node (ref "R22") (pin "1") (pinfunction "1_1") (pintype "passive"))
      (node (ref "R23") (pin "1") (pinfunction "1_1") (pintype "passive"))
      (node (ref "R24") (pin "1") (pinfunction "1_1") (pintype "passive"))
      (node (ref "R25") (pin "1") (pinfunction "1_1") (pintype "passive"))
      (node (ref "R26") (pin "1") (pinfunction "1_1") (pintype "passive"))
      (node (ref "R27") (pin "1") (pinfunction "1_1") (pintype "passive"))
      (node (ref "R62") (pin "1") (pinfunction "1_1") (pintype "passive"))
      (node (ref "R63") (pin "1") (pinfunction "1_1") (pintype "passive"))
      (node (ref "R64") (pin "1") (pinfunction "1_1") (pintype "passive"))
      (node (ref "R65") (pin "1") (pinfunction "1_1") (pintype "passive"))
      (node (ref "R66") (pin "1") (pinfunction "1_1") (pintype "passive"))
      (node (ref "R67") (pin "1") (pinfunction "1_1") (pintype "passive"))
      (node (ref "SJ1") (pin "P$2") (pinfunction "2_P$2") (pintype "passive"))
      (node (ref "SJ10") (pin "P$2") (pinfunction "2_P$2") (pintype "passive"))
      (node (ref "SJ4") (pin "P$2") (pinfunction "2_P$2") (pintype "passive"))
      (node (ref "SJ7") (pin "P$2") (pinfunction "2_P$2") (pintype "passive"))
      (node (ref "U$1") (pin "5V2") (pinfunction "5V2_5V2") (pintype "power_in"))
      (node (ref "U11") (pin "10") (pinfunction "SCL_10") (pintype "input"))
      (node (ref "U11") (pin "16") (pinfunction "VCC_16") (pintype "power_in"))
      (node (ref "U13") (pin "10") (pinfunction "SCL_10") (pintype "input"))
      (node (ref "U13") (pin "16") (pinfunction "VCC_16") (pintype "power_in"))
      (node (ref "U7") (pin "3") (pinfunction "VCC_3") (pintype "power_in"))
      (node (ref "U7B") (pin "3") (pinfunction "VDD_3") (pintype "power_in"))
      (node (ref "X6") (pin "1") (pinfunction "1_1") (pintype "passive"))
    )
    (net (code "3") (name "+12V") (class "Default")
      (node (ref "C10") (pin "1") (pinfunction "1_1") (pintype "passive"))
      (node (ref "C6") (pin "1") (pinfunction "1_1") (pintype "passive"))
      (node (ref "C7") (pin "1") (pinfunction "1_1") (pintype "passive"))
      (node (ref "J3") (pin "1") (pinfunction "1_1") (pintype "passive"))
      (node (ref "JP2") (pin "7") (pinfunction "7_7") (pintype "passive"))
      (node (ref "JP4") (pin "2") (pinfunction "2_2") (pintype "passive"))
      (node (ref "SJ11") (pin "P$2") (pinfunction "2_P$2") (pintype "passive"))
      (node (ref "SJ14") (pin "P$2") (pinfunction "2_P$2") (pintype "passive"))
      (node (ref "SJ2") (pin "P$2") (pinfunction "2_P$2") (pintype "passive"))
      (node (ref "SJ5") (pin "P$2") (pinfunction "2_P$2") (pintype "passive"))
      (node (ref "SJ8") (pin "P$2") (pinfunction "2_P$2") (pintype "passive"))
      (node (ref "U10") (pin "4") (pinfunction "V+_4") (pintype "power_in"))
      (node (ref "U3") (pin "6") (pinfunction "VDD_6") (pintype "power_in"))
      (node (ref "U4") (pin "6") (pinfunction "VDD_6") (pintype "power_in"))
      (node (ref "U5") (pin "6") (pinfunction "VDD_6") (pintype "power_in"))
      (node (ref "U6") (pin "6") (pinfunction "VDD_6") (pintype "power_in"))
      (node (ref "U8") (pin "1") (pinfunction "VIN_1") (pintype "bidirectional"))
      (node (ref "U8B") (pin "5") (pinfunction "IN_5") (pintype "input"))
      (node (ref "U9") (pin "4") (pinfunction "V+_4") (pintype "power_in"))
    )
    (net (code "4") (name "/AGND") (class "Default")
      (node (ref "U$1") (pin "AGND") (pinfunction "AGND_AGND") (pintype "power_in"))
    )
    (net (code "5") (name "/AVDD") (class "Default")
      (node (ref "U$1") (pin "AVDD") (pinfunction "AVDD_AVDD") (pintype "power_in"))
    )
    (net (code "6") (name "/CANH") (class "Default")
      (node (ref "J1") (pin "1") (pinfunction "1_1") (pintype "passive"))
      (node (ref "J2") (pin "1") (pinfunction "1_1") (pintype "passive"))
      (node (ref "U7") (pin "7") (pinfunction "CANH_7") (pintype "bidirectional"))
      (node (ref "U7B") (pin "7") (pinfunction "CANH_7") (pintype "bidirectional"))
    )
    (net (code "7") (name "/CANL") (class "Default")
      (node (ref "J1") (pin "2") (pinfunction "2_2") (pintype "passive"))
      (node (ref "J2") (pin "2") (pinfunction "2_2") (pintype "passive"))
      (node (ref "U7") (pin "6") (pinfunction "CANL_6") (pintype "bidirectional"))
      (node (ref "U7B") (pin "6") (pinfunction "CANL_6") (pintype "bidirectional"))
    )
    (net (code "8") (name "/GND4") (class "Default")
      (node (ref "U$1") (pin "GND4") (pinfunction "GND4_GND4") (pintype "power_in"))
    )
    (net (code "9") (name "/PWR_POS") (class "Default")
      (node (ref "J1") (pin "8") (pinfunction "8_8") (pintype "passive"))
      (node (ref "J2") (pin "8") (pinfunction "8_8") (pintype "passive"))
      (node (ref "R40") (pin "1") (pinfunction "1_1") (pintype "passive"))
    )
    (net (code "10") (name "/U5V") (class "Default")
      (node (ref "U$1") (pin "U5V") (pinfunction "U5V_U5V") (pintype "power_in"))
    )
    (net (code "11") (name "/VBAT") (class "Default")
      (node (ref "U$1") (pin "VBAT") (pinfunction "VBAT_VBAT") (pintype "power_in"))
    )
    (net (code "12") (name "/VDD") (class "Default")
      (node (ref "U$1") (pin "VDD") (pinfunction "VDD_VDD") (pintype "power_in"))
    )
    (net (code "13") (name "CANRX") (class "Default")
      (node (ref "U$1") (pin "PB8") (pinfunction "PB8_PB8") (pintype "bidirectional"))
      (node (ref "U7") (pin "4") (pinfunction "RXD_4") (pintype "output"))
      (node (ref "U7B") (pin "4") (pinfunction "RXD_4") (pintype "bidirectional"))
    )
    (net (code "14") (name "CANTX") (class "Default")
      (node (ref "U$1") (pin "PB9") (pinfunction "PB9_PB9") (pintype "bidirectional"))
      (node (ref "U7") (pin "1") (pinfunction "TXD_1") (pintype "input"))
      (node (ref "U7B") (pin "1") (pinfunction "TXD_1") (pintype "bidirectional"))
    )
    (net (code "15") (name "E_CS") (class "Default")
      (node (ref "JP2") (pin "4") (pinfunction "4_4") (pintype "passive"))
      (node (ref "R23") (pin "2") (pinfunction "2_2") (pintype "passive"))
      (node (ref "U$1") (pin "PC10") (pinfunction "PC10_PC10") (pintype "bidirectional"))
    )
    (net (code "16") (name "E_LAT") (class "Default")
      (node (ref "JP2") (pin "5") (pinfunction "5_5") (pintype "passive"))
      (node (ref "R22") (pin "2") (pinfunction "2_2") (pintype "passive"))
      (node (ref "U$1") (pin "PC11") (pinfunction "PC11_PC11") (pintype "bidirectional"))
    )
    (net (code "17") (name "GND") (class "Default")
      (node (ref "C1") (pin "2") (pinfunction "2_2") (pintype "passive"))
      (node (ref "C10") (pin "2") (pinfunction "2_2") (pintype "passive"))
      (node (ref "C11") (pin "2") (pinfunction "2_2") (pintype "passive"))
      (node (ref "C2") (pin "-") (pinfunction "-_-") (pintype "passive"))
      (node (ref "C3") (pin "2") (pinfunction "2_2") (pintype "passive"))
      (node (ref "C4") (pin "2") (pinfunction "2_2") (pintype "passive"))
      (node (ref "C5") (pin "2") (pinfunction "2_2") (pintype "passive"))
      (node (ref "C6") (pin "2") (pinfunction "2_2") (pintype "passive"))
      (node (ref "C7") (pin "2") (pinfunction "2_2") (pintype "passive"))
      (node (ref "C8") (pin "2") (pinfunction "2_2") (pintype "passive"))
      (node (ref "C9") (pin "2") (pinfunction "2_2") (pintype "passive"))
      (node (ref "D1") (pin "A") (pinfunction "A_A") (pintype "passive"))
      (node (ref "J1") (pin "3") (pinfunction "3_3") (pintype "passive"))
      (node (ref "J1") (pin "6") (pinfunction "6_6") (pintype "passive"))
      (node (ref "J1") (pin "7") (pinfunction "7_7") (pintype "passive"))
      (node (ref "J2") (pin "3") (pinfunction "3_3") (pintype "passive"))
      (node (ref "J2") (pin "6") (pinfunction "6_6") (pintype "passive"))
      (node (ref "J2") (pin "7") (pinfunction "7_7") (pintype "passive"))
      (node (ref "J3") (pin "2") (pinfunction "2_2") (pintype "passive"))
      (node (ref "J3") (pin "3") (pinfunction "3_3") (pintype "passive"))
      (node (ref "JP1") (pin "4") (pinfunction "4_4") (pintype "passive"))
      (node (ref "JP2") (pin "8") (pinfunction "8_8") (pintype "passive"))
      (node (ref "JP5") (pin "5") (pinfunction "5_5") (pintype "passive"))
      (node (ref "JP5") (pin "6") (pinfunction "6_6") (pintype "passive"))
      (node (ref "JP6") (pin "5") (pinfunction "5_5") (pintype "passive"))
      (node (ref "JP6") (pin "6") (pinfunction "6_6") (pintype "passive"))
      (node (ref "JP7") (pin "5") (pinfunction "5_5") (pintype "passive"))
      (node (ref "JP7") (pin "6") (pinfunction "6_6") (pintype "passive"))
      (node (ref "JP8") (pin "5") (pinfunction "5_5") (pintype "passive"))
      (node (ref "JP8") (pin "6") (pinfunction "6_6") (pintype "passive"))
      (node (ref "PORTA") (pin "5") (pinfunction "5_5") (pintype "passive"))
      (node (ref "PORTB") (pin "5") (pinfunction "5_5") (pintype "passive"))
      (node (ref "PORTC") (pin "5") (pinfunction "5_5") (pintype "passive"))
      (node (ref "Q1") (pin "2") (pinfunction "S_2") (pintype "passive"))
      (node (ref "Q10") (pin "2") (pinfunction "S_2") (pintype "passive"))
      (node (ref "Q11") (pin "2") (pinfunction "S_2") (pintype "passive"))
      (node (ref "Q12") (pin "2") (pinfunction "S_2") (pintype "passive"))
      (node (ref "Q13") (pin "2") (pinfunction "S_2") (pintype "passive"))
      (node (ref "Q14") (pin "2") (pinfunction "S_2") (pintype "passive"))
      (node (ref "Q15") (pin "2") (pinfunction "S_2") (pintype "passive"))
      (node (ref "Q16") (pin "2") (pinfunction "S_2") (pintype "passive"))
      (node (ref "Q2") (pin "2") (pinfunction "S_2") (pintype "passive"))
      (node (ref "Q3") (pin "2") (pinfunction "S_2") (pintype "passive"))
      (node (ref "Q4") (pin "2") (pinfunction "S_2") (pintype "passive"))
      (node (ref "Q5") (pin "2") (pinfunction "S_2") (pintype "passive"))
      (node (ref "Q6") (pin "2") (pinfunction "S_2") (pintype "passive"))
      (node (ref "Q7") (pin "2") (pinfunction "S_2") (pintype "passive"))
      (node (ref "Q8") (pin "2") (pinfunction "S_2") (pintype "passive"))
      (node (ref "Q9") (pin "2") (pinfunction "S_2") (pintype "passive"))
      (node (ref "R2") (pin "1") (pinfunction "1_1") (pintype "passive"))
      (node (ref "R61") (pin "2") (pinfunction "2_2") (pintype "passive"))
      (node (ref "SJ12") (pin "P$2") (pinfunction "2_P$2") (pintype "passive"))
      (node (ref "SJ3") (pin "2") (pinfunction "2_2") (pintype "passive"))
      (node (ref "SJ6") (pin "P$2") (pinfunction "2_P$2") (pintype "passive"))
      (node (ref "SJ9") (pin "2") (pinfunction "2_2") (pintype "passive"))
      (node (ref "U$1") (pin "GND3") (pinfunction "GND3_GND3") (pintype "power_in"))
      (node (ref "U$1") (pin "GND5") (pinfunction "GND5_GND5") (pintype "power_in"))
      (node (ref "U$1") (pin "GND6") (pinfunction "GND6_GND6") (pintype "power_in"))
      (node (ref "U$1") (pin "GND7") (pinfunction "GND7_GND7") (pintype "power_in"))
      (node (ref "U$1") (pin "GND8") (pinfunction "GND8_GND8") (pintype "power_in"))
      (node (ref "U1") (pin "6") (pinfunction "INH_6") (pintype "input"))
      (node (ref "U1") (pin "8") (pinfunction "GND_8") (pintype "power_in"))
      (node (ref "U10") (pin "11") (pinfunction "V-_11") (pintype "power_in"))
      (node (ref "U11") (pin "13") (pinfunction "G_13") (pintype "input"))
      (node (ref "U11") (pin "8") (pinfunction "GND_8") (pintype "power_in"))
      (node (ref "U13") (pin "13") (pinfunction "G_13") (pintype "input"))
      (node (ref "U13") (pin "8") (pinfunction "GND_8") (pintype "power_in"))
      (node (ref "U2") (pin "6") (pinfunction "INH_6") (pintype "input"))
      (node (ref "U2") (pin "8") (pinfunction "GND_8") (pintype "power_in"))
      (node (ref "U3") (pin "3") (pinfunction "VSS_3") (pintype "power_in"))
      (node (ref "U4") (pin "3") (pinfunction "VSS_3") (pintype "power_in"))
      (node (ref "U5") (pin "3") (pinfunction "VSS_3") (pintype "power_in"))
      (node (ref "U6") (pin "3") (pinfunction "VSS_3") (pintype "power_in"))
      (node (ref "U7") (pin "2") (pinfunction "GND_2") (pintype "power_in"))
      (node (ref "U7B") (pin "2") (pinfunction "VSS_2") (pintype "power_in"))
      (node (ref "U8") (pin "4") (pinfunction "SD_4") (pintype "bidirectional"))
      (node (ref "U8") (pin "5") (pinfunction "GND1_5") (pintype "power_in"))
      (node (ref "U8") (pin "6") (pinfunction "GND2_6") (pintype "power_in"))
      (node (ref "U8") (pin "7") (pinfunction "GND3_7") (pintype "power_in"))
      (node (ref "U8") (pin "8") (pinfunction "GND4_8") (pintype "power_in"))
      (node (ref "U8B") (pin "2") (pinfunction "GNDSIG_2") (pintype "input"))
      (node (ref "U8B") (pin "3") (pinfunction "~{ON/OFF}_3") (pintype "input"))
      (node (ref "U8B") (pin "4") (pinfunction "GND_4") (pintype "power_in"))
      (node (ref "U9") (pin "11") (pinfunction "V-_11") (pintype "power_in"))
      (node (ref "X6") (pin "2") (pinfunction "2_2") (pintype "passive"))
    )
    (net (code "18") (name "I2CSCL") (class "Default")
      (node (ref "JP1") (pin "1") (pinfunction "1_1") (pintype "passive"))
      (node (ref "R62") (pin "2") (pinfunction "2_2") (pintype "passive"))
      (node (ref "U$1") (pin "PB6") (pinfunction "PB6_PB6") (pintype "bidirectional"))
    )
    (net (code "19") (name "I2CSDA") (class "Default")
      (node (ref "JP1") (pin "2") (pinfunction "2_2") (pintype "passive"))
      (node (ref "R63") (pin "2") (pinfunction "2_2") (pintype "passive"))
      (node (ref "U$1") (pin "PB7") (pinfunction "PB7_PB7") (pintype "bidirectional"))
    )
    (net (code "20") (name "ILAT") (class "Default")
      (node (ref "U$1") (pin "PA6") (pinfunction "PA6_PA6") (pintype "bidirectional"))
      (node (ref "U1") (pin "15") (pinfunction "SH/~{LD}_15") (pintype "input"))
      (node (ref "U2") (pin "15") (pinfunction "SH/~{LD}_15") (pintype "input"))
    )
    (net (code "21") (name "MISO") (class "Default")
      (node (ref "JP2") (pin "1") (pinfunction "1_1") (pintype "passive"))
      (node (ref "U$1") (pin "PB4") (pinfunction "PB4_PB4") (pintype "bidirectional"))
    )
    (net (code "22") (name "MISO2") (class "Default")
      (node (ref "SJ13") (pin "P$2") (pinfunction "2_P$2") (pintype "passive"))
      (node (ref "U$1") (pin "PC2") (pinfunction "PC2_PC2") (pintype "bidirectional"))
      (node (ref "U2") (pin "13") (pinfunction "QH_13") (pintype "output"))
    )
    (net (code "23") (name "MOSI") (class "Default")
      (node (ref "R20") (pin "1") (pinfunction "1_1") (pintype "passive"))
      (node (ref "SJ15") (pin "1") (pinfunction "1_1") (pintype "passive"))
      (node (ref "SJ17") (pin "P$2") (pinfunction "2_P$2") (pintype "passive"))
      (node (ref "U$1") (pin "PB5") (pinfunction "PB5_PB5") (pintype "bidirectional"))
      (node (ref "U11") (pin "14") (pinfunction "SER_14") (pintype "input"))
    )
    (net (code "24") (name "Net-(D2-PadA)") (class "Default")
      (node (ref "D2") (pin "A") (pinfunction "A_A") (pintype "passive"))
      (node (ref "JP4") (pin "4") (pinfunction "4_4") (pintype "passive"))
    )
    (net (code "25") (name "Net-(D2-PadC)") (class "Default")
      (node (ref "D2") (pin "C") (pinfunction "C_C") (pintype "passive"))
      (node (ref "JP4") (pin "1") (pinfunction "1_1") (pintype "passive"))
    )
    (net (code "26") (name "Net-(J1-Pad4)") (class "Default")
      (node (ref "J1") (pin "4") (pinfunction "4_4") (pintype "passive"))
      (node (ref "J2") (pin "4") (pinfunction "4_4") (pintype "passive"))
    )
    (net (code "27") (name "Net-(J1-Pad5)") (class "Default")
      (node (ref "J1") (pin "5") (pinfunction "5_5") (pintype "passive"))
      (node (ref "J2") (pin "5") (pinfunction "5_5") (pintype "passive"))
    )
    (net (code "28") (name "Net-(JP4-Pad3)") (class "Default")
      (node (ref "JP4") (pin "3") (pinfunction "3_3") (pintype "passive"))
      (node (ref "R40") (pin "2") (pinfunction "2_2") (pintype "passive"))
    )
    (net (code "29") (name "Net-(PORTA-Pad1)") (class "Default")
      (node (ref "PORTA") (pin "1") (pinfunction "1_1") (pintype "passive"))
      (node (ref "R44") (pin "2") (pinfunction "2_2") (pintype "passive"))
      (node (ref "R53") (pin "2") (pinfunction "2_2") (pintype "passive"))
      (node (ref "RN3") (pin "1") (pinfunction "1_1") (pintype "passive"))
      (node (ref "RN4") (pin "9") (pinfunction "9_9") (pintype "passive"))
      (node (ref "X1") (pin "1") (pinfunction "1_1") (pintype "passive"))
    )
    (net (code "30") (name "Net-(PORTB-Pad1)") (class "Default")
      (node (ref "PORTB") (pin "1") (pinfunction "1_1") (pintype "passive"))
      (node (ref "R35") (pin "2") (pinfunction "2_2") (pintype "passive"))
      (node (ref "R45") (pin "2") (pinfunction "2_2") (pintype "passive"))
      (node (ref "RN1") (pin "1") (pinfunction "1_1") (pintype "passive"))
      (node (ref "RN2") (pin "9") (pinfunction "9_9") (pintype "passive"))
      (node (ref "X2") (pin "1") (pinfunction "1_1") (pintype "passive"))
    )
    (net (code "31") (name "Net-(Q1-D)") (class "Default")
      (node (ref "Q1") (pin "3") (pinfunction "D_3") (pintype "passive"))
      (node (ref "U12") (pin "18") (pinfunction "O1_18") (pintype "open_collector"))
      (node (ref "X5") (pin "1") (pinfunction "1_1") (pintype "passive"))
    )
    (net (code "32") (name "Net-(Q1-G)") (class "Default")
      (node (ref "Q1") (pin "1") (pinfunction "G_1") (pintype "passive"))
      (node (ref "R3") (pin "2") (pinfunction "2_2") (pintype "passive"))
    )
    (net (code "33") (name "Net-(Q2-D)") (class "Default")
      (node (ref "Q2") (pin "3") (pinfunction "D_3") (pintype "passive"))
      (node (ref "U12") (pin "17") (pinfunction "O2_17") (pintype "open_collector"))
      (node (ref "X5") (pin "2") (pinfunction "2_2") (pintype "passive"))
    )
    (net (code "34") (name "Net-(Q2-G)") (class "Default")
      (node (ref "Q2") (pin "1") (pinfunction "G_1") (pintype "passive"))
      (node (ref "R4") (pin "2") (pinfunction "2_2") (pintype "passive"))
    )
    (net (code "35") (name "Net-(Q3-D)") (class "Default")
      (node (ref "Q3") (pin "3") (pinfunction "D_3") (pintype "passive"))
      (node (ref "U12") (pin "16") (pinfunction "O3_16") (pintype "open_collector"))
      (node (ref "X5") (pin "3") (pinfunction "3_3") (pintype "passive"))
    )
    (net (code "36") (name "Net-(Q3-G)") (class "Default")
      (node (ref "Q3") (pin "1") (pinfunction "G_1") (pintype "passive"))
      (node (ref "R5") (pin "2") (pinfunction "2_2") (pintype "passive"))
    )
    (net (code "37") (name "Net-(Q4-D)") (class "Default")
      (node (ref "Q4") (pin "3") (pinfunction "D_3") (pintype "passive"))
      (node (ref "U12") (pin "15") (pinfunction "O4_15") (pintype "open_collector"))
      (node (ref "X5") (pin "4") (pinfunction "4_4") (pintype "passive"))
    )
    (net (code "38") (name "Net-(Q4-G)") (class "Default")
      (node (ref "Q4") (pin "1") (pinfunction "G_1") (pintype "passive"))
      (node (ref "R6") (pin "2") (pinfunction "2_2") (pintype "passive"))
    )
    (net (code "39") (name "Net-(Q5-D)") (class "Default")
      (node (ref "Q5") (pin "3") (pinfunction "D_3") (pintype "passive"))
      (node (ref "U12") (pin "14") (pinfunction "O5_14") (pintype "open_collector"))
      (node (ref "X5") (pin "5") (pinfunction "5_5") (pintype "passive"))
    )
    (net (code "40") (name "Net-(Q5-G)") (class "Default")
      (node (ref "Q5") (pin "1") (pinfunction "G_1") (pintype "passive"))
      (node (ref "R7") (pin "2") (pinfunction "2_2") (pintype "passive"))
    )
    (net (code "41") (name "Net-(Q6-D)") (class "Default")
      (node (ref "Q6") (pin "3") (pinfunction "D_3") (pintype "passive"))
      (node (ref "U12") (pin "13") (pinfunction "O6_13") (pintype "open_collector"))
      (node (ref "X5") (pin "6") (pinfunction "6_6") (pintype "passive"))
    )
    (net (code "42") (name "Net-(Q6-G)") (class "Default")
      (node (ref "Q6") (pin "1") (pinfunction "G_1") (pintype "passive"))
      (node (ref "R8") (pin "2") (pinfunction "2_2") (pintype "passive"))
    )
    (net (code "43") (name "Net-(Q7-D)") (class "Default")
      (node (ref "Q7") (pin "3") (pinfunction "D_3") (pintype "passive"))
      (node (ref "U12") (pin "12") (pinfunction "O7_12") (pintype "open_collector"))
      (node (ref "X5") (pin "7") (pinfunction "7_7") (pintype "passive"))
    )
    (net (code "44") (name "Net-(Q7-G)") (class "Default")
      (node (ref "Q7") (pin "1") (pinfunction "G_1") (pintype "passive"))
      (node (ref "R9") (pin "2") (pinfunction "2_2") (pintype "passive"))
    )
    (net (code "45") (name "Net-(Q8-D)") (class "Default")
      (node (ref "Q8") (pin "3") (pinfunction "D_3") (pintype "passive"))
      (node (ref "U12") (pin "11") (pinfunction "O8_11") (pintype "open_collector"))
      (node (ref "X5") (pin "8") (pinfunction "8_8") (pintype "passive"))
    )
    (net (code "46") (name "Net-(Q8-G)") (class "Default")
      (node (ref "Q8") (pin "1") (pinfunction "G_1") (pintype "passive"))
      (node (ref "R10") (pin "2") (pinfunction "2_2") (pintype "passive"))
    )
    (net (code "47") (name "Net-(Q9-D)") (class "Default")
      (node (ref "Q9") (pin "3") (pinfunction "D_3") (pintype "passive"))
      (node (ref "U14") (pin "18") (pinfunction "O1_18") (pintype "open_collector"))
      (node (ref "X4") (pin "1") (pinfunction "1_1") (pintype "passive"))
    )
    (net (code "48") (name "Net-(Q9-G)") (class "Default")
      (node (ref "Q9") (pin "1") (pinfunction "G_1") (pintype "passive"))
      (node (ref "R11") (pin "2") (pinfunction "2_2") (pintype "passive"))
    )
    (net (code "49") (name "Net-(Q10-D)") (class "Default")
      (node (ref "Q10") (pin "3") (pinfunction "D_3") (pintype "passive"))
      (node (ref "U14") (pin "17") (pinfunction "O2_17") (pintype "open_collector"))
      (node (ref "X4") (pin "2") (pinfunction "2_2") (pintype "passive"))
    )
    (net (code "50") (name "Net-(Q10-G)") (class "Default")
      (node (ref "Q10") (pin "1") (pinfunction "G_1") (pintype "passive"))
      (node (ref "R12") (pin "2") (pinfunction "2_2") (pintype "passive"))
    )
    (net (code "51") (name "Net-(Q11-D)") (class "Default")
      (node (ref "Q11") (pin "3") (pinfunction "D_3") (pintype "passive"))
      (node (ref "U14") (pin "16") (pinfunction "O3_16") (pintype "open_collector"))
      (node (ref "X4") (pin "3") (pinfunction "3_3") (pintype "passive"))
    )
    (net (code "52") (name "Net-(Q11-G)") (class "Default")
      (node (ref "Q11") (pin "1") (pinfunction "G_1") (pintype "passive"))
      (node (ref "R13") (pin "2") (pinfunction "2_2") (pintype "passive"))
    )
    (net (code "53") (name "Net-(Q12-D)") (class "Default")
      (node (ref "Q12") (pin "3") (pinfunction "D_3") (pintype "passive"))
      (node (ref "U14") (pin "15") (pinfunction "O4_15") (pintype "open_collector"))
      (node (ref "X4") (pin "4") (pinfunction "4_4") (pintype "passive"))
    )
    (net (code "54") (name "Net-(Q12-G)") (class "Default")
      (node (ref "Q12") (pin "1") (pinfunction "G_1") (pintype "passive"))
      (node (ref "R14") (pin "2") (pinfunction "2_2") (pintype "passive"))
    )
    (net (code "55") (name "Net-(Q13-D)") (class "Default")
      (node (ref "Q13") (pin "3") (pinfunction "D_3") (pintype "passive"))
      (node (ref "U14") (pin "14") (pinfunction "O5_14") (pintype "open_collector"))
      (node (ref "X4") (pin "5") (pinfunction "5_5") (pintype "passive"))
    )
    (net (code "56") (name "Net-(Q13-G)") (class "Default")
      (node (ref "Q13") (pin "1") (pinfunction "G_1") (pintype "passive"))
      (node (ref "R15") (pin "2") (pinfunction "2_2") (pintype "passive"))
    )
    (net (code "57") (name "Net-(Q14-D)") (class "Default")
      (node (ref "Q14") (pin "3") (pinfunction "D_3") (pintype "passive"))
      (node (ref "U14") (pin "13") (pinfunction "O6_13") (pintype "open_collector"))
      (node (ref "X4") (pin "6") (pinfunction "6_6") (pintype "passive"))
    )
    (net (code "58") (name "Net-(Q14-G)") (class "Default")
      (node (ref "Q14") (pin "1") (pinfunction "G_1") (pintype "passive"))
      (node (ref "R16") (pin "2") (pinfunction "2_2") (pintype "passive"))
    )
    (net (code "59") (name "Net-(Q15-D)") (class "Default")
      (node (ref "Q15") (pin "3") (pinfunction "D_3") (pintype "passive"))
      (node (ref "U14") (pin "12") (pinfunction "O7_12") (pintype "open_collector"))
      (node (ref "X4") (pin "7") (pinfunction "7_7") (pintype "passive"))
    )
    (net (code "60") (name "Net-(Q15-G)") (class "Default")
      (node (ref "Q15") (pin "1") (pinfunction "G_1") (pintype "passive"))
      (node (ref "R17") (pin "2") (pinfunction "2_2") (pintype "passive"))
    )
    (net (code "61") (name "Net-(Q16-D)") (class "Default")
      (node (ref "Q16") (pin "3") (pinfunction "D_3") (pintype "passive"))
      (node (ref "U14") (pin "11") (pinfunction "O8_11") (pintype "open_collector"))
      (node (ref "X4") (pin "8") (pinfunction "8_8") (pintype "passive"))
    )
    (net (code "62") (name "Net-(Q16-G)") (class "Default")
      (node (ref "Q16") (pin "1") (pinfunction "G_1") (pintype "passive"))
      (node (ref "R18") (pin "2") (pinfunction "2_2") (pintype "passive"))
    )
    (net (code "63") (name "Net-(RN1A-2)") (class "Default")
      (node (ref "R35") (pin "1") (pinfunction "1_1") (pintype "passive"))
      (node (ref "RN1") (pin "16") (pinfunction "2_16") (pintype "passive"))
      (node (ref "U2") (pin "14") (pinfunction "H_14") (pintype "input"))
    )
    (net (code "64") (name "Net-(RN1B-1)") (class "Default")
      (node (ref "PORTB") (pin "2") (pinfunction "2_2") (pintype "passive"))
      (node (ref "R34") (pin "2") (pinfunction "2_2") (pintype "passive"))
      (node (ref "R46") (pin "2") (pinfunction "2_2") (pintype "passive"))
      (node (ref "RN1") (pin "2") (pinfunction "1_2") (pintype "passive"))
      (node (ref "RN2") (pin "8") (pinfunction "8_8") (pintype "passive"))
      (node (ref "X2") (pin "2") (pinfunction "2_2") (pintype "passive"))
    )
    (net (code "65") (name "Net-(RN1B-2)") (class "Default")
      (node (ref "R34") (pin "1") (pinfunction "1_1") (pintype "passive"))
      (node (ref "RN1") (pin "15") (pinfunction "2_15") (pintype "passive"))
      (node (ref "U2") (pin "12") (pinfunction "G_12") (pintype "input"))
    )
    (net (code "66") (name "Net-(RN1C-1)") (class "Default")
      (node (ref "PORTB") (pin "3") (pinfunction "3_3") (pintype "passive"))
      (node (ref "R33") (pin "2") (pinfunction "2_2") (pintype "passive"))
      (node (ref "R47") (pin "2") (pinfunction "2_2") (pintype "passive"))
      (node (ref "RN1") (pin "3") (pinfunction "1_3") (pintype "passive"))
      (node (ref "RN2") (pin "7") (pinfunction "7_7") (pintype "passive"))
      (node (ref "X2") (pin "3") (pinfunction "3_3") (pintype "passive"))
    )
    (net (code "67") (name "Net-(RN1C-2)") (class "Default")
      (node (ref "R33") (pin "1") (pinfunction "1_1") (pintype "passive"))
      (node (ref "RN1") (pin "14") (pinfunction "2_14") (pintype "passive"))
      (node (ref "U2") (pin "11") (pinfunction "F_11") (pintype "input"))
    )
    (net (code "68") (name "Net-(RN1D-1)") (class "Default")
      (node (ref "PORTB") (pin "4") (pinfunction "4_4") (pintype "passive"))
      (node (ref "R32") (pin "2") (pinfunction "2_2") (pintype "passive"))
      (node (ref "R48") (pin "2") (pinfunction "2_2") (pintype "passive"))
      (node (ref "RN1") (pin "4") (pinfunction "1_4") (pintype "passive"))
      (node (ref "RN2") (pin "6") (pinfunction "6_6") (pintype "passive"))
      (node (ref "X2") (pin "4") (pinfunction "4_4") (pintype "passive"))
    )
    (net (code "69") (name "Net-(RN1D-2)") (class "Default")
      (node (ref "R32") (pin "1") (pinfunction "1_1") (pintype "passive"))
      (node (ref "RN1") (pin "13") (pinfunction "2_13") (pintype "passive"))
      (node (ref "U2") (pin "10") (pinfunction "E_10") (pintype "input"))
    )
    (net (code "70") (name "Net-(RN1E-1)") (class "Default")
      (node (ref "PORTB") (pin "7") (pinfunction "7_7") (pintype "passive"))
      (node (ref "R31") (pin "2") (pinfunction "2_2") (pintype "passive"))
      (node (ref "R49") (pin "2") (pinfunction "2_2") (pintype "passive"))
      (node (ref "RN1") (pin "5") (pinfunction "1_5") (pintype "passive"))
      (node (ref "RN2") (pin "5") (pinfunction "5_5") (pintype "passive"))
      (node (ref "X2") (pin "5") (pinfunction "5_5") (pintype "passive"))
    )
    (net (code "71") (name "Net-(RN1E-2)") (class "Default")
      (node (ref "R31") (pin "1") (pinfunction "1_1") (pintype "passive"))
      (node (ref "RN1") (pin "12") (pinfunction "2_12") (pintype "passive"))
      (node (ref "U2") (pin "5") (pinfunction "D_5") (pintype "input"))
    )
    (net (code "72") (name "Net-(RN1F-1)") (class "Default")
      (node (ref "PORTB") (pin "8") (pinfunction "8_8") (pintype "passive"))
      (node (ref "R30") (pin "2") (pinfunction "2_2") (pintype "passive"))
      (node (ref "R50") (pin "2") (pinfunction "2_2") (pintype "passive"))
      (node (ref "RN1") (pin "6") (pinfunction "1_6") (pintype "passive"))
      (node (ref "RN2") (pin "4") (pinfunction "4_4") (pintype "passive"))
      (node (ref "X2") (pin "6") (pinfunction "6_6") (pintype "passive"))
    )
    (net (code "73") (name "Net-(RN1F-2)") (class "Default")
      (node (ref "R30") (pin "1") (pinfunction "1_1") (pintype "passive"))
      (node (ref "RN1") (pin "11") (pinfunction "2_11") (pintype "passive"))
      (node (ref "U2") (pin "4") (pinfunction "C_4") (pintype "input"))
    )
    (net (code "74") (name "Net-(RN1G-1)") (class "Default")
      (node (ref "PORTB") (pin "9") (pinfunction "9_9") (pintype "passive"))
      (node (ref "R29") (pin "2") (pinfunction "2_2") (pintype "passive"))
      (node (ref "R51") (pin "2") (pinfunction "2_2") (pintype "passive"))
      (node (ref "RN1") (pin "7") (pinfunction "1_7") (pintype "passive"))
      (node (ref "RN2") (pin "3") (pinfunction "3_3") (pintype "passive"))
      (node (ref "X2") (pin "7") (pinfunction "7_7") (pintype "passive"))
    )
    (net (code "75") (name "Net-(RN1G-2)") (class "Default")
      (node (ref "R29") (pin "1") (pinfunction "1_1") (pintype "passive"))
      (node (ref "RN1") (pin "10") (pinfunction "2_10") (pintype "passive"))
      (node (ref "U2") (pin "3") (pinfunction "B_3") (pintype "input"))
    )
    (net (code "76") (name "Net-(RN1H-1)") (class "Default")
      (node (ref "PORTB") (pin "10") (pinfunction "10_10") (pintype "passive"))
      (node (ref "R28") (pin "2") (pinfunction "2_2") (pintype "passive"))
      (node (ref "R52") (pin "2") (pinfunction "2_2") (pintype "passive"))
      (node (ref "RN1") (pin "8") (pinfunction "1_8") (pintype "passive"))
      (node (ref "RN2") (pin "2") (pinfunction "2_2") (pintype "passive"))
      (node (ref "X2") (pin "8") (pinfunction "8_8") (pintype "passive"))
    )
    (net (code "77") (name "Net-(RN1H-2)") (class "Default")
      (node (ref "R28") (pin "1") (pinfunction "1_1") (pintype "passive"))
      (node (ref "RN1") (pin "9") (pinfunction "2_9") (pintype "passive"))
      (node (ref "U2") (pin "2") (pinfunction "A_2") (pintype "input"))
    )
    (net (code "78") (name "Net-(RN3A-2)") (class "Default")
      (node (ref "R44") (pin "1") (pinfunction "1_1") (pintype "passive"))
      (node (ref "RN3") (pin "16") (pinfunction "2_16") (pintype "passive"))
      (node (ref "U1") (pin "14") (pinfunction "H_14") (pintype "input"))
    )
    (net (code "79") (name "Net-(RN3B-1)") (class "Default")
      (node (ref "PORTA") (pin "2") (pinfunction "2_2") (pintype "passive"))
      (node (ref "R43") (pin "2") (pinfunction "2_2") (pintype "passive"))
      (node (ref "R54") (pin "2") (pinfunction "2_2") (pintype "passive"))
      (node (ref "RN3") (pin "2") (pinfunction "1_2") (pintype "passive"))
      (node (ref "RN4") (pin "8") (pinfunction "8_8") (pintype "passive"))
      (node (ref "X1") (pin "2") (pinfunction "2_2") (pintype "passive"))
    )
    (net (code "80") (name "Net-(RN3B-2)") (class "Default")
      (node (ref "R43") (pin "1") (pinfunction "1_1") (pintype "passive"))
      (node (ref "RN3") (pin "15") (pinfunction "2_15") (pintype "passive"))
      (node (ref "U1") (pin "12") (pinfunction "G_12") (pintype "input"))
    )
    (net (code "81") (name "Net-(RN3C-1)") (class "Default")
      (node (ref "PORTA") (pin "3") (pinfunction "3_3") (pintype "passive"))
      (node (ref "R42") (pin "2") (pinfunction "2_2") (pintype "passive"))
      (node (ref "R55") (pin "2") (pinfunction "2_2") (pintype "passive"))
      (node (ref "RN3") (pin "3") (pinfunction "1_3") (pintype "passive"))
      (node (ref "RN4") (pin "7") (pinfunction "7_7") (pintype "passive"))
      (node (ref "X1") (pin "3") (pinfunction "3_3") (pintype "passive"))
    )
    (net (code "82") (name "Net-(RN3C-2)") (class "Default")
      (node (ref "R42") (pin "1") (pinfunction "1_1") (pintype "passive"))
      (node (ref "RN3") (pin "14") (pinfunction "2_14") (pintype "passive"))
      (node (ref "U1") (pin "11") (pinfunction "F_11") (pintype "input"))
    )
    (net (code "83") (name "Net-(RN3D-1)") (class "Default")
      (node (ref "PORTA") (pin "4") (pinfunction "4_4") (pintype "passive"))
      (node (ref "R41") (pin "2") (pinfunction "2_2") (pintype "passive"))
      (node (ref "R56") (pin "2") (pinfunction "2_2") (pintype "passive"))
      (node (ref "RN3") (pin "4") (pinfunction "1_4") (pintype "passive"))
      (node (ref "RN4") (pin "6") (pinfunction "6_6") (pintype "passive"))
      (node (ref "X1") (pin "4") (pinfunction "4_4") (pintype "passive"))
    )
    (net (code "84") (name "Net-(RN3D-2)") (class "Default")
      (node (ref "R41") (pin "1") (pinfunction "1_1") (pintype "passive"))
      (node (ref "RN3") (pin "13") (pinfunction "2_13") (pintype "passive"))
      (node (ref "U1") (pin "10") (pinfunction "E_10") (pintype "input"))
    )
    (net (code "85") (name "Net-(RN3E-1)") (class "Default")
      (node (ref "PORTA") (pin "7") (pinfunction "7_7") (pintype "passive"))
      (node (ref "R39") (pin "2") (pinfunction "2_2") (pintype "passive"))
      (node (ref "R57") (pin "2") (pinfunction "2_2") (pintype "passive"))
      (node (ref "RN3") (pin "5") (pinfunction "1_5") (pintype "passive"))
      (node (ref "RN4") (pin "5") (pinfunction "5_5") (pintype "passive"))
      (node (ref "X1") (pin "5") (pinfunction "5_5") (pintype "passive"))
    )
    (net (code "86") (name "Net-(RN3E-2)") (class "Default")
      (node (ref "R39") (pin "1") (pinfunction "1_1") (pintype "passive"))
      (node (ref "RN3") (pin "12") (pinfunction "2_12") (pintype "passive"))
      (node (ref "U1") (pin "5") (pinfunction "D_5") (pintype "input"))
    )
    (net (code "87") (name "Net-(RN3F-1)") (class "Default")
      (node (ref "PORTA") (pin "8") (pinfunction "8_8") (pintype "passive"))
      (node (ref "R38") (pin "2") (pinfunction "2_2") (pintype "passive"))
      (node (ref "R58") (pin "2") (pinfunction "2_2") (pintype "passive"))
      (node (ref "RN3") (pin "6") (pinfunction "1_6") (pintype "passive"))
      (node (ref "RN4") (pin "4") (pinfunction "4_4") (pintype "passive"))
      (node (ref "X1") (pin "6") (pinfunction "6_6") (pintype "passive"))
    )
    (net (code "88") (name "Net-(RN3F-2)") (class "Default")
      (node (ref "R38") (pin "1") (pinfunction "1_1") (pintype "passive"))
      (node (ref "RN3") (pin "11") (pinfunction "2_11") (pintype "passive"))
      (node (ref "U1") (pin "4") (pinfunction "C_4") (pintype "input"))
    )
    (net (code "89") (name "Net-(RN3G-1)") (class "Default")
      (node (ref "PORTA") (pin "9") (pinfunction "9_9") (pintype "passive"))
      (node (ref "R37") (pin "2") (pinfunction "2_2") (pintype "passive"))
      (node (ref "R59") (pin "2") (pinfunction "2_2") (pintype "passive"))
      (node (ref "RN3") (pin "7") (pinfunction "1_7") (pintype "passive"))
      (node (ref "RN4") (pin "3") (pinfunction "3_3") (pintype "passive"))
      (node (ref "X1") (pin "7") (pinfunction "7_7") (pintype "passive"))
    )
    (net (code "90") (name "Net-(RN3G-2)") (class "Default")
      (node (ref "R37") (pin "1") (pinfunction "1_1") (pintype "passive"))
      (node (ref "RN3") (pin "10") (pinfunction "2_10") (pintype "passive"))
      (node (ref "U1") (pin "3") (pinfunction "B_3") (pintype "input"))
    )
    (net (code "91") (name "Net-(RN3H-1)") (class "Default")
      (node (ref "PORTA") (pin "10") (pinfunction "10_10") (pintype "passive"))
      (node (ref "R36") (pin "2") (pinfunction "2_2") (pintype "passive"))
      (node (ref "R60") (pin "2") (pinfunction "2_2") (pintype "passive"))
      (node (ref "RN3") (pin "8") (pinfunction "1_8") (pintype "passive"))
      (node (ref "RN4") (pin "2") (pinfunction "2_2") (pintype "passive"))
      (node (ref "X1") (pin "8") (pinfunction "8_8") (pintype "passive"))
    )
    (net (code "92") (name "Net-(RN3H-2)") (class "Default")
      (node (ref "R36") (pin "1") (pinfunction "1_1") (pintype "passive"))
      (node (ref "RN3") (pin "9") (pinfunction "2_9") (pintype "passive"))
      (node (ref "U1") (pin "2") (pinfunction "A_2") (pintype "input"))
    )
    (net (code "93") (name "Net-(SJ1-1)") (class "Default")
      (node (ref "SJ1") (pin "P$1") (pinfunction "1_P$1") (pintype "passive"))
      (node (ref "SJ2") (pin "P$1") (pinfunction "1_P$1") (pintype "passive"))
      (node (ref "SJ3") (pin "1") (pinfunction "1_1") (pintype "passive"))
      (node (ref "U12") (pin "9") (pinfunction "GND_9") (pintype "power_in"))
    )
    (net (code "94") (name "Net-(SJ4-1)") (class "Default")
      (node (ref "SJ4") (pin "P$1") (pinfunction "1_P$1") (pintype "passive"))
      (node (ref "SJ5") (pin "P$1") (pinfunction "1_P$1") (pintype "passive"))
      (node (ref "SJ6") (pin "P$1") (pinfunction "1_P$1") (pintype "passive"))
      (node (ref "U12") (pin "10") (pinfunction "CD+_10") (pintype "passive"))
    )
    (net (code "95") (name "Net-(SJ7-1)") (class "Default")
      (node (ref "SJ7") (pin "P$1") (pinfunction "1_P$1") (pintype "passive"))
      (node (ref "SJ8") (pin "P$1") (pinfunction "1_P$1") (pintype "passive"))
      (node (ref "SJ9") (pin "1") (pinfunction "1_1") (pintype "passive"))
      (node (ref "U14") (pin "9") (pinfunction "GND_9") (pintype "power_in"))
    )
    (net (code "96") (name "Net-(SJ10-1)") (class "Default")
      (node (ref "SJ10") (pin "P$1") (pinfunction "1_P$1") (pintype "passive"))
      (node (ref "SJ11") (pin "P$1") (pinfunction "1_P$1") (pintype "passive"))
      (node (ref "SJ12") (pin "P$1") (pinfunction "1_P$1") (pintype "passive"))
      (node (ref "U14") (pin "10") (pinfunction "CD+_10") (pintype "passive"))
    )
    (net (code "97") (name "Net-(SJ13-1)") (class "Default")
      (node (ref "SJ13") (pin "P$1") (pinfunction "1_P$1") (pintype "passive"))
      (node (ref "U$1") (pin "PB14") (pinfunction "PB14_PB14") (pintype "bidirectional"))
    )
    (net (code "98") (name "Net-(SJ14-1)") (class "Default")
      (node (ref "SJ14") (pin "P$1") (pinfunction "1_P$1") (pintype "passive"))
      (node (ref "U$1") (pin "VIN2") (pinfunction "VIN2_VIN2") (pintype "power_in"))
    )
    (net (code "99") (name "Net-(SJ16-2)") (class "Default")
      (node (ref "JP2") (pin "2") (pinfunction "2_2") (pintype "passive"))
      (node (ref "SJ15") (pin "2") (pinfunction "2_2") (pintype "passive"))
      (node (ref "SJ16") (pin "P$2") (pinfunction "2_P$2") (pintype "passive"))
    )
    (net (code "100") (name "Net-(SJ18-2)") (class "Default")
      (node (ref "SJ18") (pin "P$2") (pinfunction "2_P$2") (pintype "passive"))
      (node (ref "U7") (pin "5") (pinfunction "VREF_5") (pintype "output"))
      (node (ref "U7B") (pin "5") (pinfunction "VREF_5") (pintype "bidirectional"))
    )
    (net (code "101") (name "Net-(U3A-O)") (class "Default")
      (node (ref "PORTC") (pin "1") (pinfunction "1_1") (pintype "passive"))
      (node (ref "U3") (pin "7") (pinfunction "O_7") (pintype "output"))
      (node (ref "U9") (pin "7") (pinfunction "OUT_7") (pintype "output"))
      (node (ref "X3") (pin "1") (pinfunction "1_1") (pintype "passive"))
    )
    (net (code "102") (name "Net-(U3B-O)") (class "Default")
      (node (ref "PORTC") (pin "2") (pinfunction "2_2") (pintype "passive"))
      (node (ref "U3") (pin "5") (pinfunction "O_5") (pintype "output"))
      (node (ref "U9") (pin "8") (pinfunction "OUT_8") (pintype "output"))
      (node (ref "X3") (pin "2") (pinfunction "2_2") (pintype "passive"))
    )
    (net (code "103") (name "Net-(U4A-O)") (class "Default")
      (node (ref "PORTC") (pin "4") (pinfunction "4_4") (pintype "passive"))
      (node (ref "U4") (pin "7") (pinfunction "O_7") (pintype "output"))
      (node (ref "U9") (pin "14") (pinfunction "OUT_14") (pintype "output"))
      (node (ref "X3") (pin "4") (pinfunction "4_4") (pintype "passive"))
    )
    (net (code "104") (name "Net-(U4B-O)") (class "Default")
      (node (ref "PORTC") (pin "3") (pinfunction "3_3") (pintype "passive"))
      (node (ref "U4") (pin "5") (pinfunction "O_5") (pintype "output"))
      (node (ref "U9") (pin "1") (pinfunction "OUT_1") (pintype "output"))
      (node (ref "X3") (pin "3") (pinfunction "3_3") (pintype "passive"))
    )
    (net (code "105") (name "Net-(U7-RS)") (class "Default")
      (node (ref "R61") (pin "1") (pinfunction "1_1") (pintype "passive"))
      (node (ref "U7") (pin "8") (pinfunction "RS_8") (pintype "input"))
      (node (ref "U7B") (pin "8") (pinfunction "RS_8") (pintype "bidirectional"))
    )
    (net (code "106") (name "Net-(U8-VOUT)") (class "Default")
      (node (ref "D1") (pin "C") (pinfunction "C_C") (pintype "passive"))
      (node (ref "L1") (pin "2") (pinfunction "2_2") (pintype "passive"))
      (node (ref "U8") (pin "2") (pinfunction "VOUT_2") (pintype "bidirectional"))
      (node (ref "U8B") (pin "7") (pinfunction "OUT_7") (pintype "passive"))
    )
    (net (code "107") (name "Net-(U10A--IN)") (class "Default")
      (node (ref "R1") (pin "1") (pinfunction "1_1") (pintype "passive"))
      (node (ref "R2") (pin "2") (pinfunction "2_2") (pintype "passive"))
      (node (ref "U10") (pin "13") (pinfunction "-IN_13") (pintype "input"))
      (node (ref "U10") (pin "2") (pinfunction "-IN_2") (pintype "input"))
      (node (ref "U10") (pin "6") (pinfunction "-IN_6") (pintype "input"))
      (node (ref "U10") (pin "9") (pinfunction "-IN_9") (pintype "input"))
      (node (ref "U9") (pin "13") (pinfunction "-IN_13") (pintype "input"))
      (node (ref "U9") (pin "2") (pinfunction "-IN_2") (pintype "input"))
      (node (ref "U9") (pin "6") (pinfunction "-IN_6") (pintype "input"))
      (node (ref "U9") (pin "9") (pinfunction "-IN_9") (pintype "input"))
    )
    (net (code "108") (name "Net-(U10A-OUT)") (class "Default")
      (node (ref "PORTC") (pin "9") (pinfunction "9_9") (pintype "passive"))
      (node (ref "U10") (pin "1") (pinfunction "OUT_1") (pintype "output"))
      (node (ref "U6") (pin "5") (pinfunction "O_5") (pintype "output"))
      (node (ref "X3") (pin "7") (pinfunction "7_7") (pintype "passive"))
    )
    (net (code "109") (name "Net-(U10B-OUT)") (class "Default")
      (node (ref "PORTC") (pin "7") (pinfunction "7_7") (pintype "passive"))
      (node (ref "U10") (pin "7") (pinfunction "OUT_7") (pintype "output"))
      (node (ref "U5") (pin "7") (pinfunction "O_7") (pintype "output"))
      (node (ref "X3") (pin "5") (pinfunction "5_5") (pintype "passive"))
    )
    (net (code "110") (name "Net-(U10C-OUT)") (class "Default")
      (node (ref "PORTC") (pin "8") (pinfunction "8_8") (pintype "passive"))
      (node (ref "U10") (pin "8") (pinfunction "OUT_8") (pintype "output"))
      (node (ref "U5") (pin "5") (pinfunction "O_5") (pintype "output"))
      (node (ref "X3") (pin "6") (pinfunction "6_6") (pintype "passive"))
    )
    (net (code "111") (name "Net-(U10D-OUT)") (class "Default")
      (node (ref "PORTC") (pin "10") (pinfunction "10_10") (pintype "passive"))
      (node (ref "U10") (pin "14") (pinfunction "OUT_14") (pintype "output"))
      (node (ref "U6") (pin "7") (pinfunction "O_7") (pintype "output"))
      (node (ref "X3") (pin "8") (pinfunction "8_8") (pintype "passive"))
    )
    (net (code "112") (name "Net-(U11A-QA)") (class "Default")
      (node (ref "R3") (pin "1") (pinfunction "1_1") (pintype "passive"))
      (node (ref "U11") (pin "15") (pinfunction "QA_15") (pintype "tri_state"))
      (node (ref "U12") (pin "1") (pinfunction "I1_1") (pintype "input"))
    )
    (net (code "113") (name "Net-(U11A-QB)") (class "Default")
      (node (ref "R4") (pin "1") (pinfunction "1_1") (pintype "passive"))
      (node (ref "U11") (pin "1") (pinfunction "QB_1") (pintype "tri_state"))
      (node (ref "U12") (pin "2") (pinfunction "I2_2") (pintype "input"))
    )
    (net (code "114") (name "Net-(U11A-QC)") (class "Default")
      (node (ref "R5") (pin "1") (pinfunction "1_1") (pintype "passive"))
      (node (ref "U11") (pin "2") (pinfunction "QC_2") (pintype "tri_state"))
      (node (ref "U12") (pin "3") (pinfunction "I3_3") (pintype "input"))
    )
    (net (code "115") (name "Net-(U11A-QD)") (class "Default")
      (node (ref "R6") (pin "1") (pinfunction "1_1") (pintype "passive"))
      (node (ref "U11") (pin "3") (pinfunction "QD_3") (pintype "tri_state"))
      (node (ref "U12") (pin "4") (pinfunction "I4_4") (pintype "input"))
    )
    (net (code "116") (name "Net-(U11A-QE)") (class "Default")
      (node (ref "R7") (pin "1") (pinfunction "1_1") (pintype "passive"))
      (node (ref "U11") (pin "4") (pinfunction "QE_4") (pintype "tri_state"))
      (node (ref "U12") (pin "5") (pinfunction "I5_5") (pintype "input"))
    )
    (net (code "117") (name "Net-(U11A-QF)") (class "Default")
      (node (ref "R8") (pin "1") (pinfunction "1_1") (pintype "passive"))
      (node (ref "U11") (pin "5") (pinfunction "QF_5") (pintype "tri_state"))
      (node (ref "U12") (pin "6") (pinfunction "I6_6") (pintype "input"))
    )
    (net (code "118") (name "Net-(U11A-QG)") (class "Default")
      (node (ref "R9") (pin "1") (pinfunction "1_1") (pintype "passive"))
      (node (ref "U11") (pin "6") (pinfunction "QG_6") (pintype "tri_state"))
      (node (ref "U12") (pin "7") (pinfunction "I7_7") (pintype "input"))
    )
    (net (code "119") (name "Net-(U11A-QH)") (class "Default")
      (node (ref "R10") (pin "1") (pinfunction "1_1") (pintype "passive"))
      (node (ref "U11") (pin "7") (pinfunction "QH_7") (pintype "tri_state"))
      (node (ref "U12") (pin "8") (pinfunction "I8_8") (pintype "input"))
    )
    (net (code "120") (name "Net-(U13A-QA)") (class "Default")
      (node (ref "R11") (pin "1") (pinfunction "1_1") (pintype "passive"))
      (node (ref "U13") (pin "15") (pinfunction "QA_15") (pintype "tri_state"))
      (node (ref "U14") (pin "1") (pinfunction "I1_1") (pintype "input"))
    )
    (net (code "121") (name "Net-(U13A-QB)") (class "Default")
      (node (ref "R12") (pin "1") (pinfunction "1_1") (pintype "passive"))
      (node (ref "U13") (pin "1") (pinfunction "QB_1") (pintype "tri_state"))
      (node (ref "U14") (pin "2") (pinfunction "I2_2") (pintype "input"))
    )
    (net (code "122") (name "Net-(U13A-QC)") (class "Default")
      (node (ref "R13") (pin "1") (pinfunction "1_1") (pintype "passive"))
      (node (ref "U13") (pin "2") (pinfunction "QC_2") (pintype "tri_state"))
      (node (ref "U14") (pin "3") (pinfunction "I3_3") (pintype "input"))
    )
    (net (code "123") (name "Net-(U13A-QD)") (class "Default")
      (node (ref "R14") (pin "1") (pinfunction "1_1") (pintype "passive"))
      (node (ref "U13") (pin "3") (pinfunction "QD_3") (pintype "tri_state"))
      (node (ref "U14") (pin "4") (pinfunction "I4_4") (pintype "input"))
    )
    (net (code "124") (name "Net-(U13A-QE)") (class "Default")
      (node (ref "R15") (pin "1") (pinfunction "1_1") (pintype "passive"))
      (node (ref "U13") (pin "4") (pinfunction "QE_4") (pintype "tri_state"))
      (node (ref "U14") (pin "5") (pinfunction "I5_5") (pintype "input"))
    )
    (net (code "125") (name "Net-(U13A-QF)") (class "Default")
      (node (ref "R16") (pin "1") (pinfunction "1_1") (pintype "passive"))
      (node (ref "U13") (pin "5") (pinfunction "QF_5") (pintype "tri_state"))
      (node (ref "U14") (pin "6") (pinfunction "I6_6") (pintype "input"))
    )
    (net (code "126") (name "Net-(U13A-QG)") (class "Default")
      (node (ref "R17") (pin "1") (pinfunction "1_1") (pintype "passive"))
      (node (ref "U13") (pin "6") (pinfunction "QG_6") (pintype "tri_state"))
      (node (ref "U14") (pin "7") (pinfunction "I7_7") (pintype "input"))
    )
    (net (code "127") (name "Net-(U13A-QH)") (class "Default")
      (node (ref "R18") (pin "1") (pinfunction "1_1") (pintype "passive"))
      (node (ref "U13") (pin "7") (pinfunction "QH_7") (pintype "tri_state"))
      (node (ref "U14") (pin "8") (pinfunction "I8_8") (pintype "input"))
    )
    (net (code "128") (name "OLAT") (class "Default")
      (node (ref "R21") (pin "1") (pinfunction "1_1") (pintype "passive"))
      (node (ref "U$1") (pin "PA8") (pinfunction "PA8_PA8") (pintype "bidirectional"))
      (node (ref "U11") (pin "12") (pinfunction "RCK_12") (pintype "input"))
      (node (ref "U13") (pin "12") (pinfunction "RCK_12") (pintype "input"))
    )
    (net (code "129") (name "SCK") (class "Default")
      (node (ref "JP2") (pin "3") (pinfunction "3_3") (pintype "passive"))
      (node (ref "R19") (pin "1") (pinfunction "1_1") (pintype "passive"))
      (node (ref "U$1") (pin "PB3") (pinfunction "PB3_PB3") (pintype "bidirectional"))
      (node (ref "U11") (pin "11") (pinfunction "SCK_11") (pintype "input"))
      (node (ref "U13") (pin "11") (pinfunction "SCK_11") (pintype "input"))
    )
    (net (code "130") (name "SCK2") (class "Default")
      (node (ref "U$1") (pin "PB10") (pinfunction "PB10_PB10") (pintype "bidirectional"))
      (node (ref "U1") (pin "7") (pinfunction "CLK_7") (pintype "input"))
      (node (ref "U2") (pin "7") (pinfunction "CLK_7") (pintype "input"))
    )
    (net (code "131") (name "SLNK1") (class "Default")
      (node (ref "SJ17") (pin "P$1") (pinfunction "1_P$1") (pintype "passive"))
      (node (ref "U11") (pin "9") (pinfunction "QH*_9") (pintype "tri_state"))
      (node (ref "U13") (pin "14") (pinfunction "SER_14") (pintype "input"))
    )
    (net (code "132") (name "SLNK2") (class "Default")
      (node (ref "SJ16") (pin "P$1") (pinfunction "1_P$1") (pintype "passive"))
      (node (ref "U13") (pin "9") (pinfunction "QH*_9") (pintype "tri_state"))
    )
    (net (code "133") (name "SLNK3") (class "Default")
      (node (ref "U1") (pin "13") (pinfunction "QH_13") (pintype "output"))
      (node (ref "U2") (pin "1") (pinfunction "SER_1") (pintype "input"))
    )
    (net (code "134") (name "SRV1") (class "Default")
      (node (ref "JP5") (pin "2") (pinfunction "2_2") (pintype "passive"))
      (node (ref "R24") (pin "2") (pinfunction "2_2") (pintype "passive"))
      (node (ref "U$1") (pin "PC9") (pinfunction "PC9_PC9") (pintype "bidirectional"))
    )
    (net (code "135") (name "SRV2") (class "Default")
      (node (ref "JP5") (pin "1") (pinfunction "1_1") (pintype "passive"))
      (node (ref "R25") (pin "2") (pinfunction "2_2") (pintype "passive"))
      (node (ref "U$1") (pin "PC7") (pinfunction "PC7_PC7") (pintype "bidirectional"))
    )
    (net (code "136") (name "SRV3") (class "Default")
      (node (ref "JP6") (pin "2") (pinfunction "2_2") (pintype "passive"))
      (node (ref "R26") (pin "2") (pinfunction "2_2") (pintype "passive"))
      (node (ref "U$1") (pin "PC8") (pinfunction "PC8_PC8") (pintype "bidirectional"))
    )
    (net (code "137") (name "SRV4") (class "Default")
      (node (ref "JP6") (pin "1") (pinfunction "1_1") (pintype "passive"))
      (node (ref "R27") (pin "2") (pinfunction "2_2") (pintype "passive"))
      (node (ref "U$1") (pin "PC6") (pinfunction "PC6_PC6") (pintype "bidirectional"))
    )
    (net (code "138") (name "SRV5") (class "Default")
      (node (ref "JP7") (pin "2") (pinfunction "2_2") (pintype "passive"))
      (node (ref "R64") (pin "2") (pinfunction "2_2") (pintype "passive"))
      (node (ref "U$1") (pin "PF1-PH1") (pinfunction "PF1-PH1_PF1-PH1") (pintype "bidirectional"))
    )
    (net (code "139") (name "SRV6") (class "Default")
      (node (ref "JP7") (pin "1") (pinfunction "1_1") (pintype "passive"))
      (node (ref "R65") (pin "2") (pinfunction "2_2") (pintype "passive"))
      (node (ref "U$1") (pin "PA15") (pinfunction "PA15_PA15") (pintype "bidirectional"))
    )
    (net (code "140") (name "SRV7") (class "Default")
      (node (ref "JP8") (pin "2") (pinfunction "2_2") (pintype "passive"))
      (node (ref "R66") (pin "2") (pinfunction "2_2") (pintype "passive"))
      (node (ref "U$1") (pin "PC12") (pinfunction "PC12_PC12") (pintype "bidirectional"))
    )
    (net (code "141") (name "SRV8") (class "Default")
      (node (ref "JP8") (pin "1") (pinfunction "1_1") (pintype "passive"))
      (node (ref "R67") (pin "2") (pinfunction "2_2") (pintype "passive"))
      (node (ref "U$1") (pin "PD2") (pinfunction "PD2_PD2") (pintype "bidirectional"))
    )
    (net (code "142") (name "TDRV1") (class "Default")
      (node (ref "U$1") (pin "PB12") (pinfunction "PB12_PB12") (pintype "bidirectional"))
      (node (ref "U10") (pin "12") (pinfunction "+IN_12") (pintype "input"))
      (node (ref "U6") (pin "2") (pinfunction "I_2") (pintype "input"))
    )
    (net (code "143") (name "TDRV2") (class "Default")
      (node (ref "U$1") (pin "PB2") (pinfunction "PB2_PB2") (pintype "bidirectional"))
      (node (ref "U10") (pin "3") (pinfunction "+IN_3") (pintype "input"))
      (node (ref "U6") (pin "4") (pinfunction "I_4") (pintype "input"))
    )
    (net (code "144") (name "TDRV3") (class "Default")
      (node (ref "U$1") (pin "PB15") (pinfunction "PB15_PB15") (pintype "bidirectional"))
      (node (ref "U10") (pin "10") (pinfunction "+IN_10") (pintype "input"))
      (node (ref "U5") (pin "4") (pinfunction "I_4") (pintype "input"))
    )
    (net (code "145") (name "TDRV4") (class "Default")
      (node (ref "U$1") (pin "PB1") (pinfunction "PB1_PB1") (pintype "bidirectional"))
      (node (ref "U10") (pin "5") (pinfunction "+IN_5") (pintype "input"))
      (node (ref "U5") (pin "2") (pinfunction "I_2") (pintype "input"))
    )
    (net (code "146") (name "TDRV5") (class "Default")
      (node (ref "U$1") (pin "PA0") (pinfunction "PA0_PA0") (pintype "bidirectional"))
      (node (ref "U4") (pin "2") (pinfunction "I_2") (pintype "input"))
      (node (ref "U9") (pin "12") (pinfunction "+IN_12") (pintype "input"))
    )
    (net (code "147") (name "TDRV6") (class "Default")
      (node (ref "U$1") (pin "PA4") (pinfunction "PA4_PA4") (pintype "bidirectional"))
      (node (ref "U4") (pin "4") (pinfunction "I_4") (pintype "input"))
      (node (ref "U9") (pin "3") (pinfunction "+IN_3") (pintype "input"))
    )
    (net (code "148") (name "TDRV7") (class "Default")
      (node (ref "U$1") (pin "PC3") (pinfunction "PC3_PC3") (pintype "bidirectional"))
      (node (ref "U3") (pin "4") (pinfunction "I_4") (pintype "input"))
      (node (ref "U9") (pin "10") (pinfunction "+IN_10") (pintype "input"))
    )
    (net (code "149") (name "TDRV8") (class "Default")
      (node (ref "U$1") (pin "PC0") (pinfunction "PC0_PC0") (pintype "bidirectional"))
      (node (ref "U3") (pin "2") (pinfunction "I_2") (pintype "input"))
      (node (ref "U9") (pin "5") (pinfunction "+IN_5") (pintype "input"))
    )
    (net (code "150") (name "V+") (class "Default")
      (node (ref "C1") (pin "1") (pinfunction "1_1") (pintype "passive"))
      (node (ref "C2") (pin "+") (pinfunction "+_+") (pintype "passive"))
      (node (ref "L1") (pin "1") (pinfunction "1_1") (pintype "passive"))
      (node (ref "U$1") (pin "E5V") (pinfunction "E5V_E5V") (pintype "power_in"))
      (node (ref "U8") (pin "3") (pinfunction "FB_3") (pintype "bidirectional"))
      (node (ref "U8B") (pin "1") (pinfunction "FB_1") (pintype "input"))
    )
    (net (code "151") (name "unconnected-(H1-MOUNT-PadB3,3)") (class "Default")
      (node (ref "H1") (pin "B3,3") (pinfunction "MOUNT_B3,3") (pintype "passive"))
    )
    (net (code "152") (name "unconnected-(H2-MOUNT-PadB3,3)") (class "Default")
      (node (ref "H2") (pin "B3,3") (pinfunction "MOUNT_B3,3") (pintype "passive"))
    )
    (net (code "153") (name "unconnected-(H3-MOUNT-PadB3,3)") (class "Default")
      (node (ref "H3") (pin "B3,3") (pinfunction "MOUNT_B3,3") (pintype "passive"))
    )
    (net (code "154") (name "unconnected-(H4-MOUNT-PadB3,3)") (class "Default")
      (node (ref "H4") (pin "B3,3") (pinfunction "MOUNT_B3,3") (pintype "passive"))
    )
    (net (code "155") (name "unconnected-(U$1-PadBOOT0)") (class "Default")
      (node (ref "U$1") (pin "BOOT0") (pinfunction "BOOT0_BOOT0") (pintype "bidirectional"))
    )
    (net (code "156") (name "unconnected-(U$1-PadIOREF2)") (class "Default")
      (node (ref "U$1") (pin "IOREF2") (pinfunction "IOREF2_IOREF2") (pintype "input"))
    )
    (net (code "157") (name "unconnected-(U$1-PadNC1-PF7)") (class "Default")
      (node (ref "U$1") (pin "NC1-PF7") (pinfunction "NC1-PF7_NC1-PF7") (pintype "bidirectional"))
    )
    (net (code "158") (name "unconnected-(U$1-PadNC2-PF6)") (class "Default")
      (node (ref "U$1") (pin "NC2-PF6") (pinfunction "NC2-PF6_NC2-PF6") (pintype "bidirectional"))
    )
    (net (code "159") (name "unconnected-(U$1-PadNC3)") (class "Default")
      (node (ref "U$1") (pin "NC3") (pinfunction "NC3_NC3") (pintype "no_connect"))
    )
    (net (code "160") (name "unconnected-(U$1-PadNC4)") (class "Default")
      (node (ref "U$1") (pin "NC4") (pinfunction "NC4_NC4") (pintype "no_connect"))
    )
    (net (code "161") (name "unconnected-(U$1-PadNC5-PD8)") (class "Default")
      (node (ref "U$1") (pin "NC5-PD8") (pinfunction "NC5-PD8_NC5-PD8") (pintype "bidirectional"))
    )
    (net (code "162") (name "unconnected-(U$1-PadNC6-PB11)") (class "Default")
      (node (ref "U$1") (pin "NC6-PB11") (pinfunction "NC6-PB11_NC6-PB11") (pintype "no_connect"))
    )
    (net (code "163") (name "unconnected-(U$1-PadNC7-PF5)") (class "Default")
      (node (ref "U$1") (pin "NC7-PF5") (pinfunction "NC7-PF5_NC7-PF5") (pintype "bidirectional"))
    )
    (net (code "164") (name "unconnected-(U$1-PadNC8-PF4)") (class "Default")
      (node (ref "U$1") (pin "NC8-PF4") (pinfunction "NC8-PF4_NC8-PF4") (pintype "bidirectional"))
    )
    (net (code "165") (name "unconnected-(U$1-PadNRESET)") (class "Default")
      (node (ref "U$1") (pin "NRESET") (pinfunction "NRESET_NRESET") (pintype "input"))
    )
    (net (code "166") (name "unconnected-(U$1-PadPA1)") (class "Default")
      (node (ref "U$1") (pin "PA1") (pinfunction "PA1_PA1") (pintype "bidirectional"))
    )
    (net (code "167") (name "unconnected-(U$1-PadPA2)") (class "Default")
      (node (ref "U$1") (pin "PA2") (pinfunction "PA2_PA2") (pintype "bidirectional"))
    )
    (net (code "168") (name "unconnected-(U$1-PadPA3)") (class "Default")
      (node (ref "U$1") (pin "PA3") (pinfunction "PA3_PA3") (pintype "bidirectional"))
    )
    (net (code "169") (name "unconnected-(U$1-PadPA5)") (class "Default")
      (node (ref "U$1") (pin "PA5") (pinfunction "PA5_PA5") (pintype "bidirectional"))
    )
    (net (code "170") (name "unconnected-(U$1-PadPA7)") (class "Default")
      (node (ref "U$1") (pin "PA7") (pinfunction "PA7_PA7") (pintype "bidirectional"))
    )
    (net (code "171") (name "unconnected-(U$1-PadPA9)") (class "Default")
      (node (ref "U$1") (pin "PA9") (pinfunction "PA9_PA9") (pintype "bidirectional"))
    )
    (net (code "172") (name "unconnected-(U$1-PadPA10)") (class "Default")
      (node (ref "U$1") (pin "PA10") (pinfunction "PA10_PA10") (pintype "bidirectional"))
    )
    (net (code "173") (name "unconnected-(U$1-PadPA11)") (class "Default")
      (node (ref "U$1") (pin "PA11") (pinfunction "PA11_PA11") (pintype "bidirectional"))
    )
    (net (code "174") (name "unconnected-(U$1-PadPA12)") (class "Default")
      (node (ref "U$1") (pin "PA12") (pinfunction "PA12_PA12") (pintype "bidirectional"))
    )
    (net (code "175") (name "unconnected-(U$1-PadPA13)") (class "Default")
      (node (ref "U$1") (pin "PA13") (pinfunction "PA13_PA13") (pintype "bidirectional"))
    )
    (net (code "176") (name "unconnected-(U$1-PadPA14)") (class "Default")
      (node (ref "U$1") (pin "PA14") (pinfunction "PA14_PA14") (pintype "bidirectional"))
    )
    (net (code "177") (name "unconnected-(U$1-PadPB0)") (class "Default")
      (node (ref "U$1") (pin "PB0") (pinfunction "PB0_PB0") (pintype "bidirectional"))
    )
    (net (code "178") (name "unconnected-(U$1-PadPB13)") (class "Default")
      (node (ref "U$1") (pin "PB13") (pinfunction "PB13_PB13") (pintype "bidirectional"))
    )
    (net (code "179") (name "unconnected-(U$1-PadPC1)") (class "Default")
      (node (ref "U$1") (pin "PC1") (pinfunction "PC1_PC1") (pintype "bidirectional"))
    )
    (net (code "180") (name "unconnected-(U$1-PadPC4)") (class "Default")
      (node (ref "U$1") (pin "PC4") (pinfunction "PC4_PC4") (pintype "bidirectional"))
    )
    (net (code "181") (name "unconnected-(U$1-PadPC5)") (class "Default")
      (node (ref "U$1") (pin "PC5") (pinfunction "PC5_PC5") (pintype "bidirectional"))
    )
    (net (code "182") (name "unconnected-(U$1-PadPC13)") (class "Default")
      (node (ref "U$1") (pin "PC13") (pinfunction "PC13_PC13") (pintype "bidirectional"))
    )
    (net (code "183") (name "unconnected-(U$1-PadPC14)") (class "Default")
      (node (ref "U$1") (pin "PC14") (pinfunction "PC14_PC14") (pintype "bidirectional"))
    )
    (net (code "184") (name "unconnected-(U$1-PadPC15)") (class "Default")
      (node (ref "U$1") (pin "PC15") (pinfunction "PC15_PC15") (pintype "bidirectional"))
    )
    (net (code "185") (name "unconnected-(U$1-PadPF0-PH0)") (class "Default")
      (node (ref "U$1") (pin "PF0-PH0") (pinfunction "PF0-PH0_PF0-PH0") (pintype "bidirectional"))
    )
  )
)
